# Callisto_Teknic_MSO_LED_out.net
KiCad netlist of a schematic drawn in EAGLE
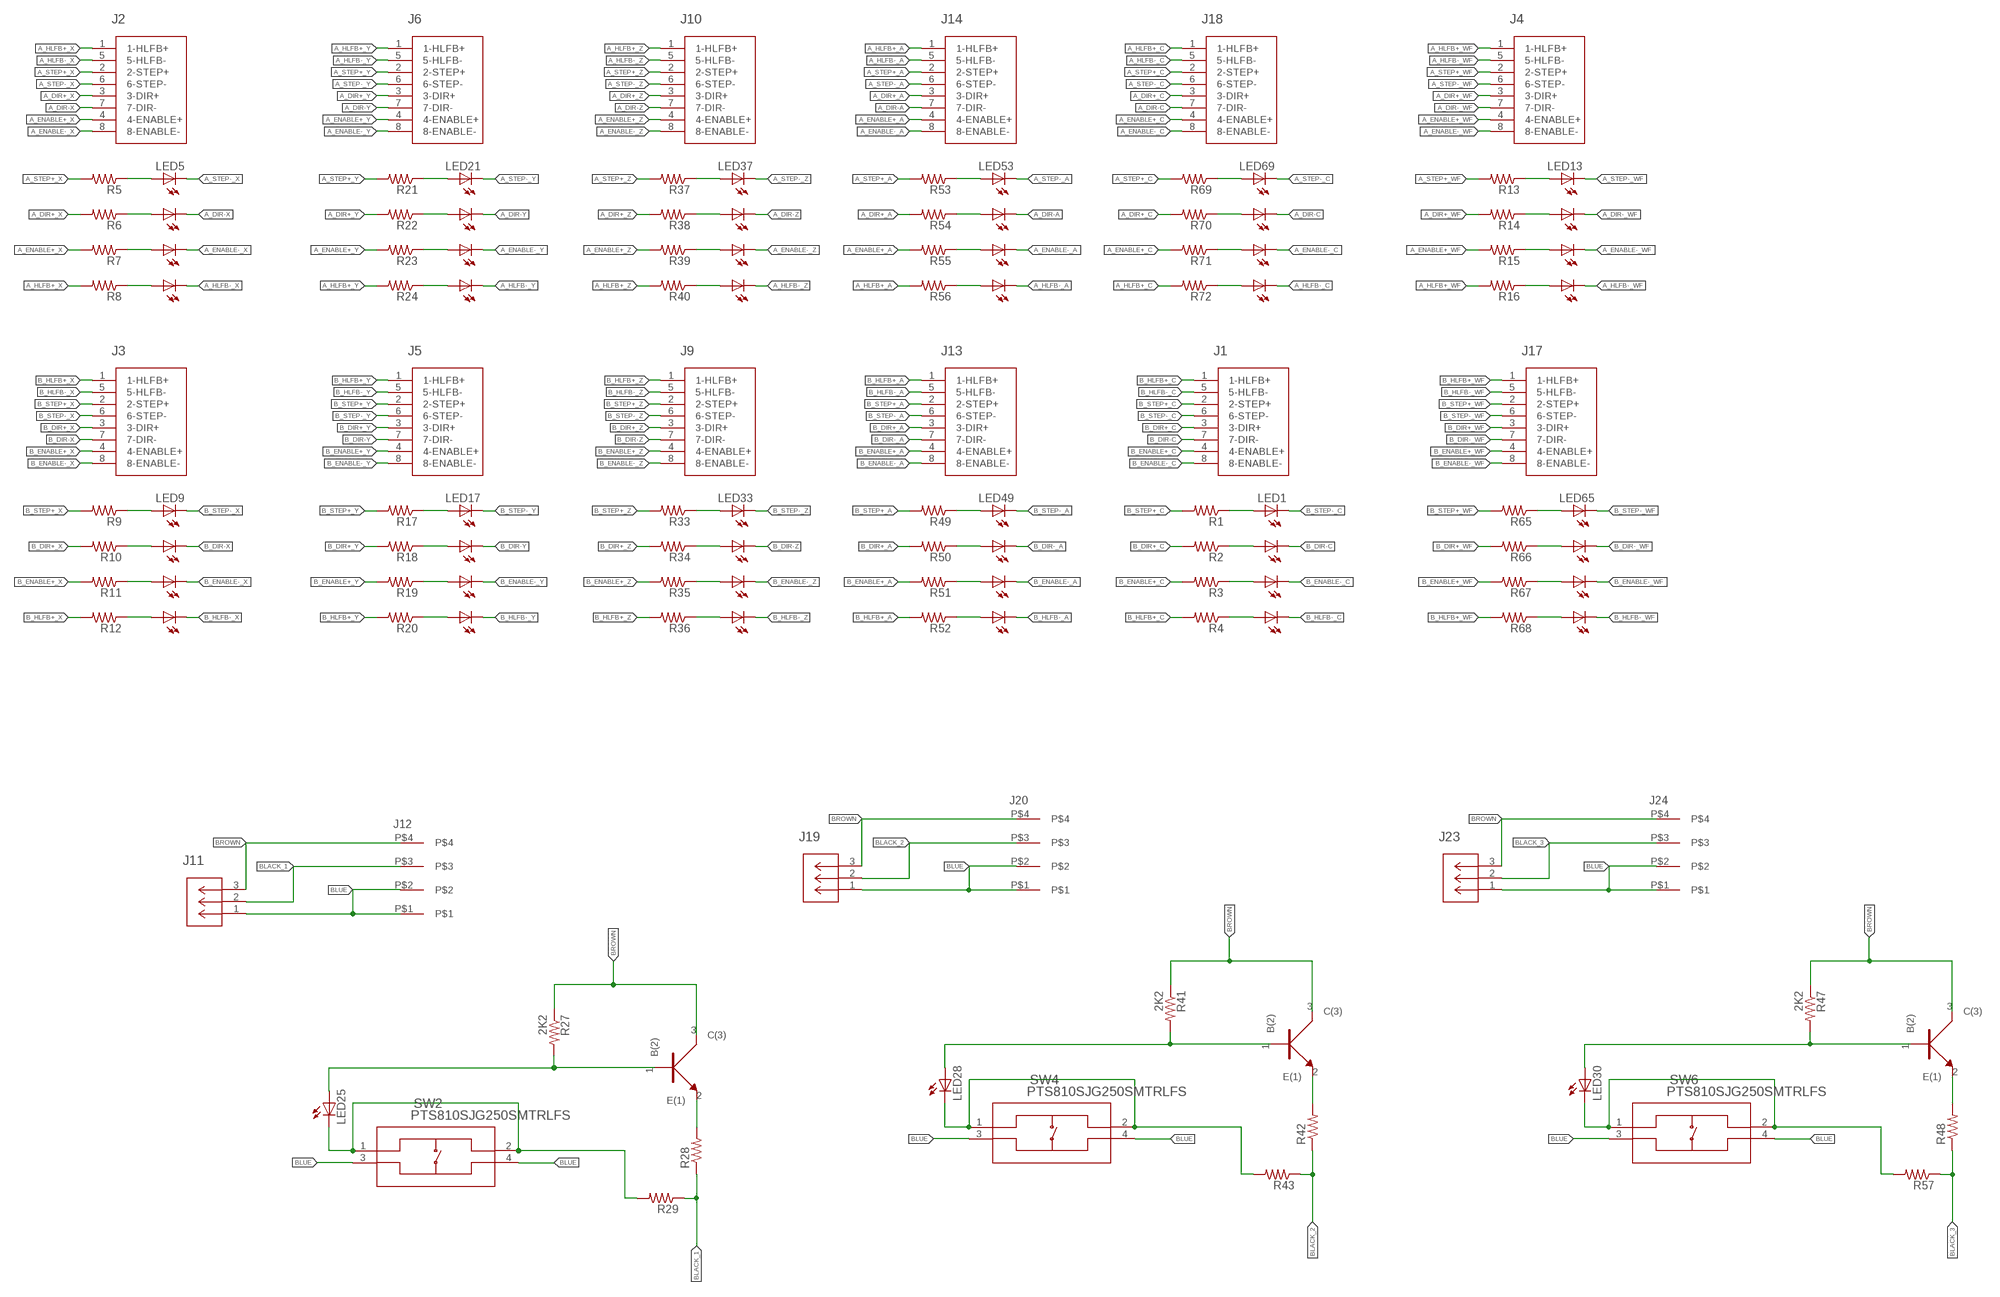
[diagram p0: schematic, sheet 1, part 1 of 2]
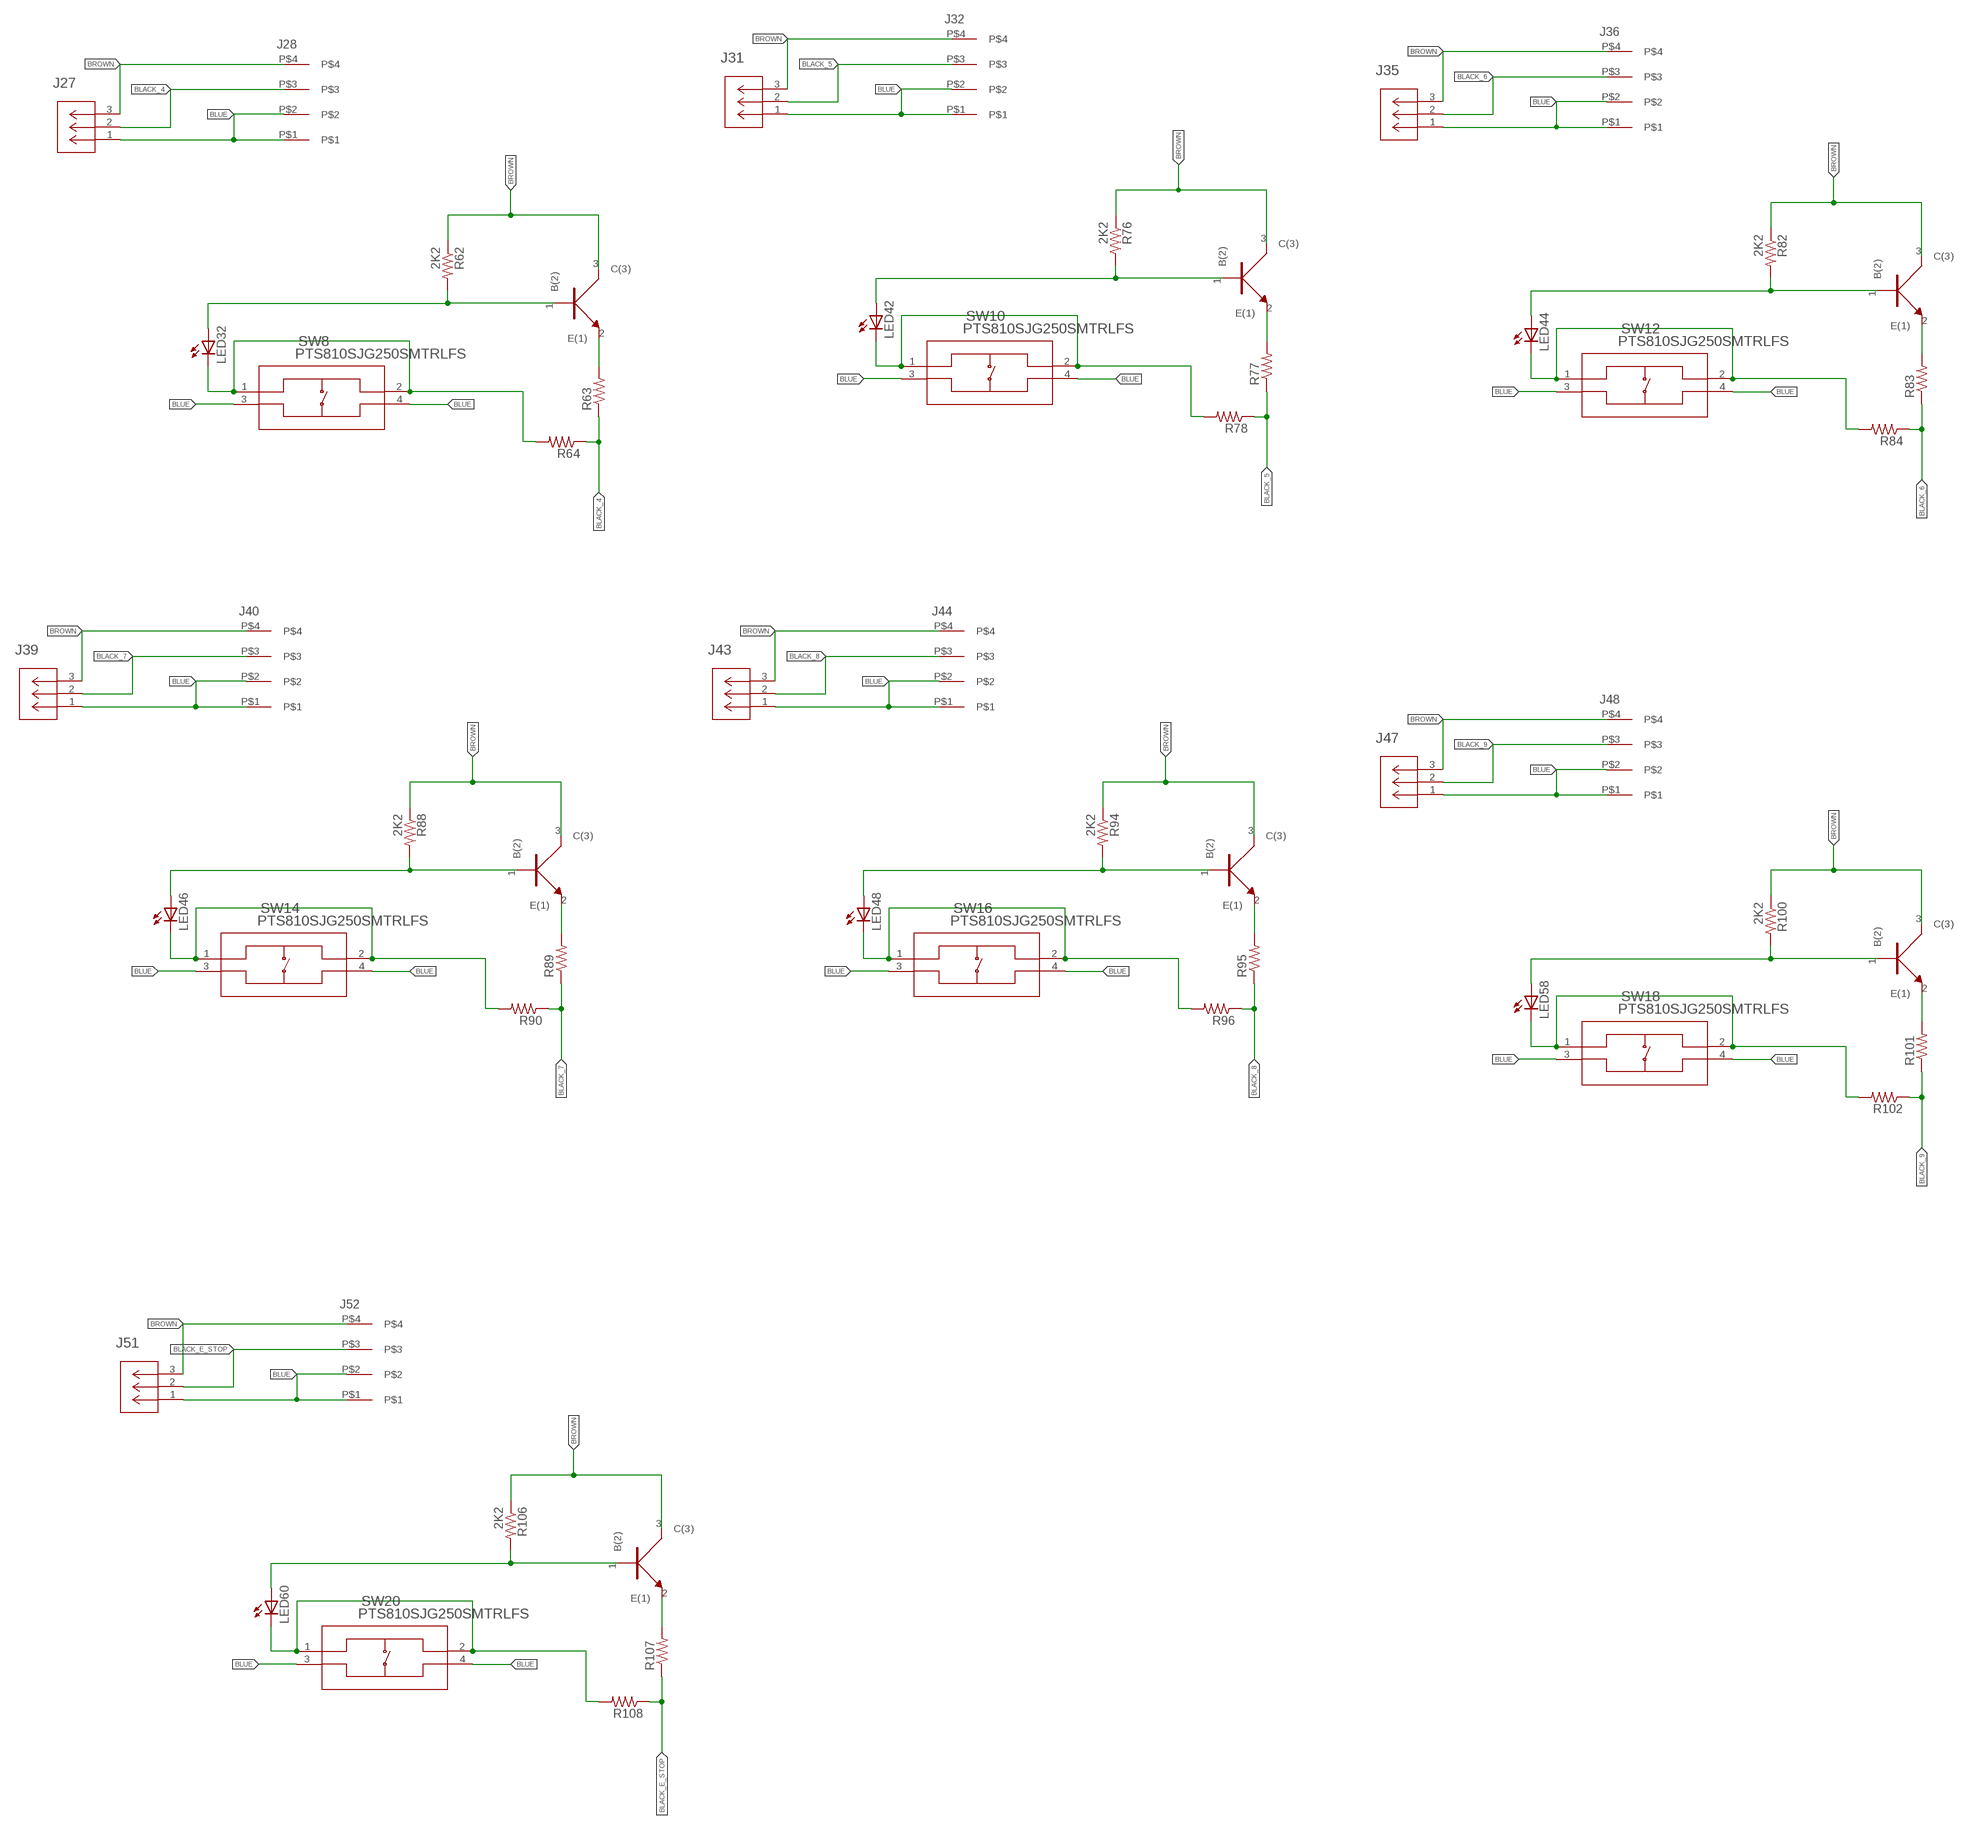
[diagram p1: schematic, sheet 1, part 2 of 2]

(export (version "E")
  (design (tool "Eeschema 10.0.6"))
  (components
    (comp (ref "J1")
      (value "TEKNIC_MOTOR_SD_8PIN")
      (footprint "eagle-import:CON_39281083")
      (fields
        (field (name "MANUFACTURER_PART_NUMBER") "39281083")
        (field (name "COPYRIGHT") "Copyright (C) 2022 Ultra Librarian. All rights reserved.")
      )
      (libsource (lib "eagle-import") (part "TEKNIC_MOTOR_SD_8PIN"))
    )
    (comp (ref "J2")
      (value "TEKNIC_MOTOR_SD_8PIN")
      (footprint "eagle-import:CON_39281083")
      (fields
        (field (name "MANUFACTURER_PART_NUMBER") "39281083")
        (field (name "COPYRIGHT") "Copyright (C) 2022 Ultra Librarian. All rights reserved.")
      )
      (libsource (lib "eagle-import") (part "TEKNIC_MOTOR_SD_8PIN"))
    )
    (comp (ref "J3")
      (value "TEKNIC_MOTOR_SD_8PIN")
      (footprint "eagle-import:CON_39281083")
      (fields
        (field (name "MANUFACTURER_PART_NUMBER") "39281083")
        (field (name "COPYRIGHT") "Copyright (C) 2022 Ultra Librarian. All rights reserved.")
      )
      (libsource (lib "eagle-import") (part "TEKNIC_MOTOR_SD_8PIN"))
    )
    (comp (ref "J4")
      (value "TEKNIC_MOTOR_SD_8PIN")
      (footprint "eagle-import:CON_39281083")
      (fields
        (field (name "MANUFACTURER_PART_NUMBER") "39281083")
        (field (name "COPYRIGHT") "Copyright (C) 2022 Ultra Librarian. All rights reserved.")
      )
      (libsource (lib "eagle-import") (part "TEKNIC_MOTOR_SD_8PIN"))
    )
    (comp (ref "J5")
      (value "TEKNIC_MOTOR_SD_8PIN")
      (footprint "eagle-import:CON_39281083")
      (fields
        (field (name "MANUFACTURER_PART_NUMBER") "39281083")
        (field (name "COPYRIGHT") "Copyright (C) 2022 Ultra Librarian. All rights reserved.")
      )
      (libsource (lib "eagle-import") (part "TEKNIC_MOTOR_SD_8PIN"))
    )
    (comp (ref "J6")
      (value "TEKNIC_MOTOR_SD_8PIN")
      (footprint "eagle-import:CON_39281083")
      (fields
        (field (name "MANUFACTURER_PART_NUMBER") "39281083")
        (field (name "COPYRIGHT") "Copyright (C) 2022 Ultra Librarian. All rights reserved.")
      )
      (libsource (lib "eagle-import") (part "TEKNIC_MOTOR_SD_8PIN"))
    )
    (comp (ref "J9")
      (value "TEKNIC_MOTOR_SD_8PIN")
      (footprint "eagle-import:CON_39281083")
      (fields
        (field (name "MANUFACTURER_PART_NUMBER") "39281083")
        (field (name "COPYRIGHT") "Copyright (C) 2022 Ultra Librarian. All rights reserved.")
      )
      (libsource (lib "eagle-import") (part "TEKNIC_MOTOR_SD_8PIN"))
    )
    (comp (ref "J10")
      (value "TEKNIC_MOTOR_SD_8PIN")
      (footprint "eagle-import:CON_39281083")
      (fields
        (field (name "MANUFACTURER_PART_NUMBER") "39281083")
        (field (name "COPYRIGHT") "Copyright (C) 2022 Ultra Librarian. All rights reserved.")
      )
      (libsource (lib "eagle-import") (part "TEKNIC_MOTOR_SD_8PIN"))
    )
    (comp (ref "J11")
      (value "CONN_530470310_PICOBLADE_X_3")
      (footprint "eagle-import:CON_530470310_MOL")
      (fields
        (field (name "MANUFACTURER_PART_NUMBER") "530470310")
        (field (name "COPYRIGHT") "Copyright (C) 2022 Ultra Librarian. All rights reserved.")
      )
      (libsource (lib "eagle-import") (part "CONN_530470310_PICOBLADE_X_3"))
    )
    (comp (ref "J12")
      (value "4-pos")
      (footprint "eagle-import:1X4_3.81MM_PITCH")
      (fields (field (name "PARTNO") "691322310004"))
      (libsource (lib "eagle-import") (part "3.81MM_1_X_4_RT_ANGLE_PLUG_HEADER"))
    )
    (comp (ref "J13")
      (value "TEKNIC_MOTOR_SD_8PIN")
      (footprint "eagle-import:CON_39281083")
      (fields
        (field (name "MANUFACTURER_PART_NUMBER") "39281083")
        (field (name "COPYRIGHT") "Copyright (C) 2022 Ultra Librarian. All rights reserved.")
      )
      (libsource (lib "eagle-import") (part "TEKNIC_MOTOR_SD_8PIN"))
    )
    (comp (ref "J14")
      (value "TEKNIC_MOTOR_SD_8PIN")
      (footprint "eagle-import:CON_39281083")
      (fields
        (field (name "MANUFACTURER_PART_NUMBER") "39281083")
        (field (name "COPYRIGHT") "Copyright (C) 2022 Ultra Librarian. All rights reserved.")
      )
      (libsource (lib "eagle-import") (part "TEKNIC_MOTOR_SD_8PIN"))
    )
    (comp (ref "J17")
      (value "TEKNIC_MOTOR_SD_8PIN")
      (footprint "eagle-import:CON_39281083")
      (fields
        (field (name "MANUFACTURER_PART_NUMBER") "39281083")
        (field (name "COPYRIGHT") "Copyright (C) 2022 Ultra Librarian. All rights reserved.")
      )
      (libsource (lib "eagle-import") (part "TEKNIC_MOTOR_SD_8PIN"))
    )
    (comp (ref "J18")
      (value "TEKNIC_MOTOR_SD_8PIN")
      (footprint "eagle-import:CON_39281083")
      (fields
        (field (name "MANUFACTURER_PART_NUMBER") "39281083")
        (field (name "COPYRIGHT") "Copyright (C) 2022 Ultra Librarian. All rights reserved.")
      )
      (libsource (lib "eagle-import") (part "TEKNIC_MOTOR_SD_8PIN"))
    )
    (comp (ref "J19")
      (value "CONN_530470310_PICOBLADE_X_3")
      (footprint "eagle-import:CON_530470310_MOL")
      (fields
        (field (name "MANUFACTURER_PART_NUMBER") "530470310")
        (field (name "COPYRIGHT") "Copyright (C) 2022 Ultra Librarian. All rights reserved.")
      )
      (libsource (lib "eagle-import") (part "CONN_530470310_PICOBLADE_X_3"))
    )
    (comp (ref "J20")
      (value "4-pos")
      (footprint "eagle-import:1X4_3.81MM_PITCH")
      (fields (field (name "PARTNO") "691322310004"))
      (libsource (lib "eagle-import") (part "3.81MM_1_X_4_RT_ANGLE_PLUG_HEADER"))
    )
    (comp (ref "J23")
      (value "CONN_530470310_PICOBLADE_X_3")
      (footprint "eagle-import:CON_530470310_MOL")
      (fields
        (field (name "MANUFACTURER_PART_NUMBER") "530470310")
        (field (name "COPYRIGHT") "Copyright (C) 2022 Ultra Librarian. All rights reserved.")
      )
      (libsource (lib "eagle-import") (part "CONN_530470310_PICOBLADE_X_3"))
    )
    (comp (ref "J24")
      (value "4-pos")
      (footprint "eagle-import:1X4_3.81MM_PITCH")
      (fields (field (name "PARTNO") "691322310004"))
      (libsource (lib "eagle-import") (part "3.81MM_1_X_4_RT_ANGLE_PLUG_HEADER"))
    )
    (comp (ref "J27")
      (value "CONN_530470310_PICOBLADE_X_3")
      (footprint "eagle-import:CON_530470310_MOL")
      (fields
        (field (name "MANUFACTURER_PART_NUMBER") "530470310")
        (field (name "COPYRIGHT") "Copyright (C) 2022 Ultra Librarian. All rights reserved.")
      )
      (libsource (lib "eagle-import") (part "CONN_530470310_PICOBLADE_X_3"))
    )
    (comp (ref "J28")
      (value "4-pos")
      (footprint "eagle-import:1X4_3.81MM_PITCH")
      (fields (field (name "PARTNO") "691322310004"))
      (libsource (lib "eagle-import") (part "3.81MM_1_X_4_RT_ANGLE_PLUG_HEADER"))
    )
    (comp (ref "J31")
      (value "CONN_530470310_PICOBLADE_X_3")
      (footprint "eagle-import:CON_530470310_MOL")
      (fields
        (field (name "MANUFACTURER_PART_NUMBER") "530470310")
        (field (name "COPYRIGHT") "Copyright (C) 2022 Ultra Librarian. All rights reserved.")
      )
      (libsource (lib "eagle-import") (part "CONN_530470310_PICOBLADE_X_3"))
    )
    (comp (ref "J32")
      (value "4-pos")
      (footprint "eagle-import:1X4_3.81MM_PITCH")
      (fields (field (name "PARTNO") "691322310004"))
      (libsource (lib "eagle-import") (part "3.81MM_1_X_4_RT_ANGLE_PLUG_HEADER"))
    )
    (comp (ref "J35")
      (value "CONN_530470310_PICOBLADE_X_3")
      (footprint "eagle-import:CON_530470310_MOL")
      (fields
        (field (name "MANUFACTURER_PART_NUMBER") "530470310")
        (field (name "COPYRIGHT") "Copyright (C) 2022 Ultra Librarian. All rights reserved.")
      )
      (libsource (lib "eagle-import") (part "CONN_530470310_PICOBLADE_X_3"))
    )
    (comp (ref "J36")
      (value "4-pos")
      (footprint "eagle-import:1X4_3.81MM_PITCH")
      (fields (field (name "PARTNO") "691322310004"))
      (libsource (lib "eagle-import") (part "3.81MM_1_X_4_RT_ANGLE_PLUG_HEADER"))
    )
    (comp (ref "J39")
      (value "CONN_530470310_PICOBLADE_X_3")
      (footprint "eagle-import:CON_530470310_MOL")
      (fields
        (field (name "MANUFACTURER_PART_NUMBER") "530470310")
        (field (name "COPYRIGHT") "Copyright (C) 2022 Ultra Librarian. All rights reserved.")
      )
      (libsource (lib "eagle-import") (part "CONN_530470310_PICOBLADE_X_3"))
    )
    (comp (ref "J40")
      (value "4-pos")
      (footprint "eagle-import:1X4_3.81MM_PITCH")
      (fields (field (name "PARTNO") "691322310004"))
      (libsource (lib "eagle-import") (part "3.81MM_1_X_4_RT_ANGLE_PLUG_HEADER"))
    )
    (comp (ref "J43")
      (value "CONN_530470310_PICOBLADE_X_3")
      (footprint "eagle-import:CON_530470310_MOL")
      (fields
        (field (name "MANUFACTURER_PART_NUMBER") "530470310")
        (field (name "COPYRIGHT") "Copyright (C) 2022 Ultra Librarian. All rights reserved.")
      )
      (libsource (lib "eagle-import") (part "CONN_530470310_PICOBLADE_X_3"))
    )
    (comp (ref "J44")
      (value "4-pos")
      (footprint "eagle-import:1X4_3.81MM_PITCH")
      (fields (field (name "PARTNO") "691322310004"))
      (libsource (lib "eagle-import") (part "3.81MM_1_X_4_RT_ANGLE_PLUG_HEADER"))
    )
    (comp (ref "J47")
      (value "CONN_530470310_PICOBLADE_X_3")
      (footprint "eagle-import:CON_530470310_MOL")
      (fields
        (field (name "MANUFACTURER_PART_NUMBER") "530470310")
        (field (name "COPYRIGHT") "Copyright (C) 2022 Ultra Librarian. All rights reserved.")
      )
      (libsource (lib "eagle-import") (part "CONN_530470310_PICOBLADE_X_3"))
    )
    (comp (ref "J48")
      (value "4-pos")
      (footprint "eagle-import:1X4_3.81MM_PITCH")
      (fields (field (name "PARTNO") "691322310004"))
      (libsource (lib "eagle-import") (part "3.81MM_1_X_4_RT_ANGLE_PLUG_HEADER"))
    )
    (comp (ref "J51")
      (value "CONN_530470310_PICOBLADE_X_3")
      (footprint "eagle-import:CON_530470310_MOL")
      (fields
        (field (name "MANUFACTURER_PART_NUMBER") "530470310")
        (field (name "COPYRIGHT") "Copyright (C) 2022 Ultra Librarian. All rights reserved.")
      )
      (libsource (lib "eagle-import") (part "CONN_530470310_PICOBLADE_X_3"))
    )
    (comp (ref "J52")
      (value "4-pos")
      (footprint "eagle-import:1X4_3.81MM_PITCH")
      (fields (field (name "PARTNO") "691322310004"))
      (libsource (lib "eagle-import") (part "3.81MM_1_X_4_RT_ANGLE_PLUG_HEADER"))
    )
    (comp (ref "LED1")
      (value "Green")
      (footprint "eagle-import:0805")
      (fields (field (name "PARTNO") "LG R971-KN-1"))
      (libsource (lib "eagle-import") (part "LED_0805_GREEN"))
    )
    (comp (ref "LED2")
      (value "Green")
      (footprint "eagle-import:0805")
      (fields (field (name "PARTNO") "LG R971-KN-1"))
      (libsource (lib "eagle-import") (part "LED_0805_GREEN"))
    )
    (comp (ref "LED3")
      (value "Green")
      (footprint "eagle-import:0805")
      (fields (field (name "PARTNO") "LG R971-KN-1"))
      (libsource (lib "eagle-import") (part "LED_0805_GREEN"))
    )
    (comp (ref "LED4")
      (value "Green")
      (footprint "eagle-import:0805")
      (fields (field (name "PARTNO") "LG R971-KN-1"))
      (libsource (lib "eagle-import") (part "LED_0805_GREEN"))
    )
    (comp (ref "LED5")
      (value "Green")
      (footprint "eagle-import:0805")
      (fields (field (name "PARTNO") "LG R971-KN-1"))
      (libsource (lib "eagle-import") (part "LED_0805_GREEN"))
    )
    (comp (ref "LED6")
      (value "Green")
      (footprint "eagle-import:0805")
      (fields (field (name "PARTNO") "LG R971-KN-1"))
      (libsource (lib "eagle-import") (part "LED_0805_GREEN"))
    )
    (comp (ref "LED7")
      (value "Green")
      (footprint "eagle-import:0805")
      (fields (field (name "PARTNO") "LG R971-KN-1"))
      (libsource (lib "eagle-import") (part "LED_0805_GREEN"))
    )
    (comp (ref "LED8")
      (value "Green")
      (footprint "eagle-import:0805")
      (fields (field (name "PARTNO") "LG R971-KN-1"))
      (libsource (lib "eagle-import") (part "LED_0805_GREEN"))
    )
    (comp (ref "LED9")
      (value "Green")
      (footprint "eagle-import:0805")
      (fields (field (name "PARTNO") "LG R971-KN-1"))
      (libsource (lib "eagle-import") (part "LED_0805_GREEN"))
    )
    (comp (ref "LED10")
      (value "Green")
      (footprint "eagle-import:0805")
      (fields (field (name "PARTNO") "LG R971-KN-1"))
      (libsource (lib "eagle-import") (part "LED_0805_GREEN"))
    )
    (comp (ref "LED11")
      (value "Green")
      (footprint "eagle-import:0805")
      (fields (field (name "PARTNO") "LG R971-KN-1"))
      (libsource (lib "eagle-import") (part "LED_0805_GREEN"))
    )
    (comp (ref "LED12")
      (value "Green")
      (footprint "eagle-import:0805")
      (fields (field (name "PARTNO") "LG R971-KN-1"))
      (libsource (lib "eagle-import") (part "LED_0805_GREEN"))
    )
    (comp (ref "LED13")
      (value "Green")
      (footprint "eagle-import:0805")
      (fields (field (name "PARTNO") "LG R971-KN-1"))
      (libsource (lib "eagle-import") (part "LED_0805_GREEN"))
    )
    (comp (ref "LED14")
      (value "Green")
      (footprint "eagle-import:0805")
      (fields (field (name "PARTNO") "LG R971-KN-1"))
      (libsource (lib "eagle-import") (part "LED_0805_GREEN"))
    )
    (comp (ref "LED15")
      (value "Green")
      (footprint "eagle-import:0805")
      (fields (field (name "PARTNO") "LG R971-KN-1"))
      (libsource (lib "eagle-import") (part "LED_0805_GREEN"))
    )
    (comp (ref "LED16")
      (value "Green")
      (footprint "eagle-import:0805")
      (fields (field (name "PARTNO") "LG R971-KN-1"))
      (libsource (lib "eagle-import") (part "LED_0805_GREEN"))
    )
    (comp (ref "LED17")
      (value "Green")
      (footprint "eagle-import:0805")
      (fields (field (name "PARTNO") "LG R971-KN-1"))
      (libsource (lib "eagle-import") (part "LED_0805_GREEN"))
    )
    (comp (ref "LED18")
      (value "Green")
      (footprint "eagle-import:0805")
      (fields (field (name "PARTNO") "LG R971-KN-1"))
      (libsource (lib "eagle-import") (part "LED_0805_GREEN"))
    )
    (comp (ref "LED19")
      (value "Green")
      (footprint "eagle-import:0805")
      (fields (field (name "PARTNO") "LG R971-KN-1"))
      (libsource (lib "eagle-import") (part "LED_0805_GREEN"))
    )
    (comp (ref "LED20")
      (value "Green")
      (footprint "eagle-import:0805")
      (fields (field (name "PARTNO") "LG R971-KN-1"))
      (libsource (lib "eagle-import") (part "LED_0805_GREEN"))
    )
    (comp (ref "LED21")
      (value "Green")
      (footprint "eagle-import:0805")
      (fields (field (name "PARTNO") "LG R971-KN-1"))
      (libsource (lib "eagle-import") (part "LED_0805_GREEN"))
    )
    (comp (ref "LED22")
      (value "Green")
      (footprint "eagle-import:0805")
      (fields (field (name "PARTNO") "LG R971-KN-1"))
      (libsource (lib "eagle-import") (part "LED_0805_GREEN"))
    )
    (comp (ref "LED23")
      (value "Green")
      (footprint "eagle-import:0805")
      (fields (field (name "PARTNO") "LG R971-KN-1"))
      (libsource (lib "eagle-import") (part "LED_0805_GREEN"))
    )
    (comp (ref "LED24")
      (value "Green")
      (footprint "eagle-import:0805")
      (fields (field (name "PARTNO") "LG R971-KN-1"))
      (libsource (lib "eagle-import") (part "LED_0805_GREEN"))
    )
    (comp (ref "LED25")
      (value "Green")
      (footprint "eagle-import:0805")
      (fields (field (name "PARTNO") "LG R971-KN-1"))
      (libsource (lib "eagle-import") (part "LED_0805_GREEN"))
    )
    (comp (ref "LED28")
      (value "Green")
      (footprint "eagle-import:0805")
      (fields (field (name "PARTNO") "LG R971-KN-1"))
      (libsource (lib "eagle-import") (part "LED_0805_GREEN"))
    )
    (comp (ref "LED30")
      (value "Green")
      (footprint "eagle-import:0805")
      (fields (field (name "PARTNO") "LG R971-KN-1"))
      (libsource (lib "eagle-import") (part "LED_0805_GREEN"))
    )
    (comp (ref "LED32")
      (value "Green")
      (footprint "eagle-import:0805")
      (fields (field (name "PARTNO") "LG R971-KN-1"))
      (libsource (lib "eagle-import") (part "LED_0805_GREEN"))
    )
    (comp (ref "LED33")
      (value "Green")
      (footprint "eagle-import:0805")
      (fields (field (name "PARTNO") "LG R971-KN-1"))
      (libsource (lib "eagle-import") (part "LED_0805_GREEN"))
    )
    (comp (ref "LED34")
      (value "Green")
      (footprint "eagle-import:0805")
      (fields (field (name "PARTNO") "LG R971-KN-1"))
      (libsource (lib "eagle-import") (part "LED_0805_GREEN"))
    )
    (comp (ref "LED35")
      (value "Green")
      (footprint "eagle-import:0805")
      (fields (field (name "PARTNO") "LG R971-KN-1"))
      (libsource (lib "eagle-import") (part "LED_0805_GREEN"))
    )
    (comp (ref "LED36")
      (value "Green")
      (footprint "eagle-import:0805")
      (fields (field (name "PARTNO") "LG R971-KN-1"))
      (libsource (lib "eagle-import") (part "LED_0805_GREEN"))
    )
    (comp (ref "LED37")
      (value "Green")
      (footprint "eagle-import:0805")
      (fields (field (name "PARTNO") "LG R971-KN-1"))
      (libsource (lib "eagle-import") (part "LED_0805_GREEN"))
    )
    (comp (ref "LED38")
      (value "Green")
      (footprint "eagle-import:0805")
      (fields (field (name "PARTNO") "LG R971-KN-1"))
      (libsource (lib "eagle-import") (part "LED_0805_GREEN"))
    )
    (comp (ref "LED39")
      (value "Green")
      (footprint "eagle-import:0805")
      (fields (field (name "PARTNO") "LG R971-KN-1"))
      (libsource (lib "eagle-import") (part "LED_0805_GREEN"))
    )
    (comp (ref "LED40")
      (value "Green")
      (footprint "eagle-import:0805")
      (fields (field (name "PARTNO") "LG R971-KN-1"))
      (libsource (lib "eagle-import") (part "LED_0805_GREEN"))
    )
    (comp (ref "LED42")
      (value "Green")
      (footprint "eagle-import:0805")
      (fields (field (name "PARTNO") "LG R971-KN-1"))
      (libsource (lib "eagle-import") (part "LED_0805_GREEN"))
    )
    (comp (ref "LED44")
      (value "Green")
      (footprint "eagle-import:0805")
      (fields (field (name "PARTNO") "LG R971-KN-1"))
      (libsource (lib "eagle-import") (part "LED_0805_GREEN"))
    )
    (comp (ref "LED46")
      (value "Green")
      (footprint "eagle-import:0805")
      (fields (field (name "PARTNO") "LG R971-KN-1"))
      (libsource (lib "eagle-import") (part "LED_0805_GREEN"))
    )
    (comp (ref "LED48")
      (value "Green")
      (footprint "eagle-import:0805")
      (fields (field (name "PARTNO") "LG R971-KN-1"))
      (libsource (lib "eagle-import") (part "LED_0805_GREEN"))
    )
    (comp (ref "LED49")
      (value "Green")
      (footprint "eagle-import:0805")
      (fields (field (name "PARTNO") "LG R971-KN-1"))
      (libsource (lib "eagle-import") (part "LED_0805_GREEN"))
    )
    (comp (ref "LED50")
      (value "Green")
      (footprint "eagle-import:0805")
      (fields (field (name "PARTNO") "LG R971-KN-1"))
      (libsource (lib "eagle-import") (part "LED_0805_GREEN"))
    )
    (comp (ref "LED51")
      (value "Green")
      (footprint "eagle-import:0805")
      (fields (field (name "PARTNO") "LG R971-KN-1"))
      (libsource (lib "eagle-import") (part "LED_0805_GREEN"))
    )
    (comp (ref "LED52")
      (value "Green")
      (footprint "eagle-import:0805")
      (fields (field (name "PARTNO") "LG R971-KN-1"))
      (libsource (lib "eagle-import") (part "LED_0805_GREEN"))
    )
    (comp (ref "LED53")
      (value "Green")
      (footprint "eagle-import:0805")
      (fields (field (name "PARTNO") "LG R971-KN-1"))
      (libsource (lib "eagle-import") (part "LED_0805_GREEN"))
    )
    (comp (ref "LED54")
      (value "Green")
      (footprint "eagle-import:0805")
      (fields (field (name "PARTNO") "LG R971-KN-1"))
      (libsource (lib "eagle-import") (part "LED_0805_GREEN"))
    )
    (comp (ref "LED55")
      (value "Green")
      (footprint "eagle-import:0805")
      (fields (field (name "PARTNO") "LG R971-KN-1"))
      (libsource (lib "eagle-import") (part "LED_0805_GREEN"))
    )
    (comp (ref "LED56")
      (value "Green")
      (footprint "eagle-import:0805")
      (fields (field (name "PARTNO") "LG R971-KN-1"))
      (libsource (lib "eagle-import") (part "LED_0805_GREEN"))
    )
    (comp (ref "LED58")
      (value "Green")
      (footprint "eagle-import:0805")
      (fields (field (name "PARTNO") "LG R971-KN-1"))
      (libsource (lib "eagle-import") (part "LED_0805_GREEN"))
    )
    (comp (ref "LED60")
      (value "Green")
      (footprint "eagle-import:0805")
      (fields (field (name "PARTNO") "LG R971-KN-1"))
      (libsource (lib "eagle-import") (part "LED_0805_GREEN"))
    )
    (comp (ref "LED65")
      (value "Green")
      (footprint "eagle-import:0805")
      (fields (field (name "PARTNO") "LG R971-KN-1"))
      (libsource (lib "eagle-import") (part "LED_0805_GREEN"))
    )
    (comp (ref "LED66")
      (value "Green")
      (footprint "eagle-import:0805")
      (fields (field (name "PARTNO") "LG R971-KN-1"))
      (libsource (lib "eagle-import") (part "LED_0805_GREEN"))
    )
    (comp (ref "LED67")
      (value "Green")
      (footprint "eagle-import:0805")
      (fields (field (name "PARTNO") "LG R971-KN-1"))
      (libsource (lib "eagle-import") (part "LED_0805_GREEN"))
    )
    (comp (ref "LED68")
      (value "Green")
      (footprint "eagle-import:0805")
      (fields (field (name "PARTNO") "LG R971-KN-1"))
      (libsource (lib "eagle-import") (part "LED_0805_GREEN"))
    )
    (comp (ref "LED69")
      (value "Green")
      (footprint "eagle-import:0805")
      (fields (field (name "PARTNO") "LG R971-KN-1"))
      (libsource (lib "eagle-import") (part "LED_0805_GREEN"))
    )
    (comp (ref "LED70")
      (value "Green")
      (footprint "eagle-import:0805")
      (fields (field (name "PARTNO") "LG R971-KN-1"))
      (libsource (lib "eagle-import") (part "LED_0805_GREEN"))
    )
    (comp (ref "LED71")
      (value "Green")
      (footprint "eagle-import:0805")
      (fields (field (name "PARTNO") "LG R971-KN-1"))
      (libsource (lib "eagle-import") (part "LED_0805_GREEN"))
    )
    (comp (ref "LED72")
      (value "Green")
      (footprint "eagle-import:0805")
      (fields (field (name "PARTNO") "LG R971-KN-1"))
      (libsource (lib "eagle-import") (part "LED_0805_GREEN"))
    )
    (comp (ref "R1")
      (value "R_0805")
      (footprint "eagle-import:0805")
      (libsource (lib "eagle-import") (part "R_0805"))
    )
    (comp (ref "R2")
      (value "R_0805")
      (footprint "eagle-import:0805")
      (libsource (lib "eagle-import") (part "R_0805"))
    )
    (comp (ref "R3")
      (value "R_0805")
      (footprint "eagle-import:0805")
      (libsource (lib "eagle-import") (part "R_0805"))
    )
    (comp (ref "R4")
      (value "R_0805")
      (footprint "eagle-import:0805")
      (libsource (lib "eagle-import") (part "R_0805"))
    )
    (comp (ref "R5")
      (value "R_0805")
      (footprint "eagle-import:0805")
      (libsource (lib "eagle-import") (part "R_0805"))
    )
    (comp (ref "R6")
      (value "R_0805")
      (footprint "eagle-import:0805")
      (libsource (lib "eagle-import") (part "R_0805"))
    )
    (comp (ref "R7")
      (value "R_0805")
      (footprint "eagle-import:0805")
      (libsource (lib "eagle-import") (part "R_0805"))
    )
    (comp (ref "R8")
      (value "R_0805")
      (footprint "eagle-import:0805")
      (libsource (lib "eagle-import") (part "R_0805"))
    )
    (comp (ref "R9")
      (value "R_0805")
      (footprint "eagle-import:0805")
      (libsource (lib "eagle-import") (part "R_0805"))
    )
    (comp (ref "R10")
      (value "R_0805")
      (footprint "eagle-import:0805")
      (libsource (lib "eagle-import") (part "R_0805"))
    )
    (comp (ref "R11")
      (value "R_0805")
      (footprint "eagle-import:0805")
      (libsource (lib "eagle-import") (part "R_0805"))
    )
    (comp (ref "R12")
      (value "R_0805")
      (footprint "eagle-import:0805")
      (libsource (lib "eagle-import") (part "R_0805"))
    )
    (comp (ref "R13")
      (value "R_0805")
      (footprint "eagle-import:0805")
      (libsource (lib "eagle-import") (part "R_0805"))
    )
    (comp (ref "R14")
      (value "R_0805")
      (footprint "eagle-import:0805")
      (libsource (lib "eagle-import") (part "R_0805"))
    )
    (comp (ref "R15")
      (value "R_0805")
      (footprint "eagle-import:0805")
      (libsource (lib "eagle-import") (part "R_0805"))
    )
    (comp (ref "R16")
      (value "R_0805")
      (footprint "eagle-import:0805")
      (libsource (lib "eagle-import") (part "R_0805"))
    )
    (comp (ref "R17")
      (value "R_0805")
      (footprint "eagle-import:0805")
      (libsource (lib "eagle-import") (part "R_0805"))
    )
    (comp (ref "R18")
      (value "R_0805")
      (footprint "eagle-import:0805")
      (libsource (lib "eagle-import") (part "R_0805"))
    )
    (comp (ref "R19")
      (value "R_0805")
      (footprint "eagle-import:0805")
      (libsource (lib "eagle-import") (part "R_0805"))
    )
    (comp (ref "R20")
      (value "R_0805")
      (footprint "eagle-import:0805")
      (libsource (lib "eagle-import") (part "R_0805"))
    )
    (comp (ref "R21")
      (value "R_0805")
      (footprint "eagle-import:0805")
      (libsource (lib "eagle-import") (part "R_0805"))
    )
    (comp (ref "R22")
      (value "R_0805")
      (footprint "eagle-import:0805")
      (libsource (lib "eagle-import") (part "R_0805"))
    )
    (comp (ref "R23")
      (value "R_0805")
      (footprint "eagle-import:0805")
      (libsource (lib "eagle-import") (part "R_0805"))
    )
    (comp (ref "R24")
      (value "R_0805")
      (footprint "eagle-import:0805")
      (libsource (lib "eagle-import") (part "R_0805"))
    )
    (comp (ref "R27")
      (value "2K2")
      (footprint "eagle-import:0402")
      (libsource (lib "eagle-import") (part "R_0402"))
    )
    (comp (ref "R28")
      (value "R_0402")
      (footprint "eagle-import:0402")
      (libsource (lib "eagle-import") (part "R_0402"))
    )
    (comp (ref "R29")
      (value "R_0402")
      (footprint "eagle-import:0402")
      (libsource (lib "eagle-import") (part "R_0402"))
    )
    (comp (ref "R33")
      (value "R_0805")
      (footprint "eagle-import:0805")
      (libsource (lib "eagle-import") (part "R_0805"))
    )
    (comp (ref "R34")
      (value "R_0805")
      (footprint "eagle-import:0805")
      (libsource (lib "eagle-import") (part "R_0805"))
    )
    (comp (ref "R35")
      (value "R_0805")
      (footprint "eagle-import:0805")
      (libsource (lib "eagle-import") (part "R_0805"))
    )
    (comp (ref "R36")
      (value "R_0805")
      (footprint "eagle-import:0805")
      (libsource (lib "eagle-import") (part "R_0805"))
    )
    (comp (ref "R37")
      (value "R_0805")
      (footprint "eagle-import:0805")
      (libsource (lib "eagle-import") (part "R_0805"))
    )
    (comp (ref "R38")
      (value "R_0805")
      (footprint "eagle-import:0805")
      (libsource (lib "eagle-import") (part "R_0805"))
    )
    (comp (ref "R39")
      (value "R_0805")
      (footprint "eagle-import:0805")
      (libsource (lib "eagle-import") (part "R_0805"))
    )
    (comp (ref "R40")
      (value "R_0805")
      (footprint "eagle-import:0805")
      (libsource (lib "eagle-import") (part "R_0805"))
    )
    (comp (ref "R41")
      (value "2K2")
      (footprint "eagle-import:0402")
      (libsource (lib "eagle-import") (part "R_0402"))
    )
    (comp (ref "R42")
      (value "R_0402")
      (footprint "eagle-import:0402")
      (libsource (lib "eagle-import") (part "R_0402"))
    )
    (comp (ref "R43")
      (value "R_0402")
      (footprint "eagle-import:0402")
      (libsource (lib "eagle-import") (part "R_0402"))
    )
    (comp (ref "R47")
      (value "2K2")
      (footprint "eagle-import:0402")
      (libsource (lib "eagle-import") (part "R_0402"))
    )
    (comp (ref "R48")
      (value "R_0402")
      (footprint "eagle-import:0402")
      (libsource (lib "eagle-import") (part "R_0402"))
    )
    (comp (ref "R49")
      (value "R_0805")
      (footprint "eagle-import:0805")
      (libsource (lib "eagle-import") (part "R_0805"))
    )
    (comp (ref "R50")
      (value "R_0805")
      (footprint "eagle-import:0805")
      (libsource (lib "eagle-import") (part "R_0805"))
    )
    (comp (ref "R51")
      (value "R_0805")
      (footprint "eagle-import:0805")
      (libsource (lib "eagle-import") (part "R_0805"))
    )
    (comp (ref "R52")
      (value "R_0805")
      (footprint "eagle-import:0805")
      (libsource (lib "eagle-import") (part "R_0805"))
    )
    (comp (ref "R53")
      (value "R_0805")
      (footprint "eagle-import:0805")
      (libsource (lib "eagle-import") (part "R_0805"))
    )
    (comp (ref "R54")
      (value "R_0805")
      (footprint "eagle-import:0805")
      (libsource (lib "eagle-import") (part "R_0805"))
    )
    (comp (ref "R55")
      (value "R_0805")
      (footprint "eagle-import:0805")
      (libsource (lib "eagle-import") (part "R_0805"))
    )
    (comp (ref "R56")
      (value "R_0805")
      (footprint "eagle-import:0805")
      (libsource (lib "eagle-import") (part "R_0805"))
    )
    (comp (ref "R57")
      (value "R_0402")
      (footprint "eagle-import:0402")
      (libsource (lib "eagle-import") (part "R_0402"))
    )
    (comp (ref "R62")
      (value "2K2")
      (footprint "eagle-import:0402")
      (libsource (lib "eagle-import") (part "R_0402"))
    )
    (comp (ref "R63")
      (value "R_0402")
      (footprint "eagle-import:0402")
      (libsource (lib "eagle-import") (part "R_0402"))
    )
    (comp (ref "R64")
      (value "R_0402")
      (footprint "eagle-import:0402")
      (libsource (lib "eagle-import") (part "R_0402"))
    )
    (comp (ref "R65")
      (value "R_0805")
      (footprint "eagle-import:0805")
      (libsource (lib "eagle-import") (part "R_0805"))
    )
    (comp (ref "R66")
      (value "R_0805")
      (footprint "eagle-import:0805")
      (libsource (lib "eagle-import") (part "R_0805"))
    )
    (comp (ref "R67")
      (value "R_0805")
      (footprint "eagle-import:0805")
      (libsource (lib "eagle-import") (part "R_0805"))
    )
    (comp (ref "R68")
      (value "R_0805")
      (footprint "eagle-import:0805")
      (libsource (lib "eagle-import") (part "R_0805"))
    )
    (comp (ref "R69")
      (value "R_0805")
      (footprint "eagle-import:0805")
      (libsource (lib "eagle-import") (part "R_0805"))
    )
    (comp (ref "R70")
      (value "R_0805")
      (footprint "eagle-import:0805")
      (libsource (lib "eagle-import") (part "R_0805"))
    )
    (comp (ref "R71")
      (value "R_0805")
      (footprint "eagle-import:0805")
      (libsource (lib "eagle-import") (part "R_0805"))
    )
    (comp (ref "R72")
      (value "R_0805")
      (footprint "eagle-import:0805")
      (libsource (lib "eagle-import") (part "R_0805"))
    )
    (comp (ref "R76")
      (value "2K2")
      (footprint "eagle-import:0402")
      (libsource (lib "eagle-import") (part "R_0402"))
    )
    (comp (ref "R77")
      (value "R_0402")
      (footprint "eagle-import:0402")
      (libsource (lib "eagle-import") (part "R_0402"))
    )
    (comp (ref "R78")
      (value "R_0402")
      (footprint "eagle-import:0402")
      (libsource (lib "eagle-import") (part "R_0402"))
    )
    (comp (ref "R82")
      (value "2K2")
      (footprint "eagle-import:0402")
      (libsource (lib "eagle-import") (part "R_0402"))
    )
    (comp (ref "R83")
      (value "R_0402")
      (footprint "eagle-import:0402")
      (libsource (lib "eagle-import") (part "R_0402"))
    )
    (comp (ref "R84")
      (value "R_0402")
      (footprint "eagle-import:0402")
      (libsource (lib "eagle-import") (part "R_0402"))
    )
    (comp (ref "R88")
      (value "2K2")
      (footprint "eagle-import:0402")
      (libsource (lib "eagle-import") (part "R_0402"))
    )
    (comp (ref "R89")
      (value "R_0402")
      (footprint "eagle-import:0402")
      (libsource (lib "eagle-import") (part "R_0402"))
    )
    (comp (ref "R90")
      (value "R_0402")
      (footprint "eagle-import:0402")
      (libsource (lib "eagle-import") (part "R_0402"))
    )
    (comp (ref "R94")
      (value "2K2")
      (footprint "eagle-import:0402")
      (libsource (lib "eagle-import") (part "R_0402"))
    )
    (comp (ref "R95")
      (value "R_0402")
      (footprint "eagle-import:0402")
      (libsource (lib "eagle-import") (part "R_0402"))
    )
    (comp (ref "R96")
      (value "R_0402")
      (footprint "eagle-import:0402")
      (libsource (lib "eagle-import") (part "R_0402"))
    )
    (comp (ref "R100")
      (value "2K2")
      (footprint "eagle-import:0402")
      (libsource (lib "eagle-import") (part "R_0402"))
    )
    (comp (ref "R101")
      (value "R_0402")
      (footprint "eagle-import:0402")
      (libsource (lib "eagle-import") (part "R_0402"))
    )
    (comp (ref "R102")
      (value "R_0402")
      (footprint "eagle-import:0402")
      (libsource (lib "eagle-import") (part "R_0402"))
    )
    (comp (ref "R106")
      (value "2K2")
      (footprint "eagle-import:0402")
      (libsource (lib "eagle-import") (part "R_0402"))
    )
    (comp (ref "R107")
      (value "R_0402")
      (footprint "eagle-import:0402")
      (libsource (lib "eagle-import") (part "R_0402"))
    )
    (comp (ref "R108")
      (value "R_0402")
      (footprint "eagle-import:0402")
      (libsource (lib "eagle-import") (part "R_0402"))
    )
    (comp (ref "SW2")
      (value "PTS810SJG250SMTRLFS")
      (footprint "eagle-import:PTS810")
      (fields (field (name "COPYRIGHT") "Copyright (C) 2018 Accelerated Designs. All rights reserved"))
      (libsource (lib "eagle-import") (part "PTS810SJG250SMTRLFS"))
    )
    (comp (ref "SW4")
      (value "PTS810SJG250SMTRLFS")
      (footprint "eagle-import:PTS810")
      (fields (field (name "COPYRIGHT") "Copyright (C) 2018 Accelerated Designs. All rights reserved"))
      (libsource (lib "eagle-import") (part "PTS810SJG250SMTRLFS"))
    )
    (comp (ref "SW6")
      (value "PTS810SJG250SMTRLFS")
      (footprint "eagle-import:PTS810")
      (fields (field (name "COPYRIGHT") "Copyright (C) 2018 Accelerated Designs. All rights reserved"))
      (libsource (lib "eagle-import") (part "PTS810SJG250SMTRLFS"))
    )
    (comp (ref "SW8")
      (value "PTS810SJG250SMTRLFS")
      (footprint "eagle-import:PTS810")
      (fields (field (name "COPYRIGHT") "Copyright (C) 2018 Accelerated Designs. All rights reserved"))
      (libsource (lib "eagle-import") (part "PTS810SJG250SMTRLFS"))
    )
    (comp (ref "SW10")
      (value "PTS810SJG250SMTRLFS")
      (footprint "eagle-import:PTS810")
      (fields (field (name "COPYRIGHT") "Copyright (C) 2018 Accelerated Designs. All rights reserved"))
      (libsource (lib "eagle-import") (part "PTS810SJG250SMTRLFS"))
    )
    (comp (ref "SW12")
      (value "PTS810SJG250SMTRLFS")
      (footprint "eagle-import:PTS810")
      (fields (field (name "COPYRIGHT") "Copyright (C) 2018 Accelerated Designs. All rights reserved"))
      (libsource (lib "eagle-import") (part "PTS810SJG250SMTRLFS"))
    )
    (comp (ref "SW14")
      (value "PTS810SJG250SMTRLFS")
      (footprint "eagle-import:PTS810")
      (fields (field (name "COPYRIGHT") "Copyright (C) 2018 Accelerated Designs. All rights reserved"))
      (libsource (lib "eagle-import") (part "PTS810SJG250SMTRLFS"))
    )
    (comp (ref "SW16")
      (value "PTS810SJG250SMTRLFS")
      (footprint "eagle-import:PTS810")
      (fields (field (name "COPYRIGHT") "Copyright (C) 2018 Accelerated Designs. All rights reserved"))
      (libsource (lib "eagle-import") (part "PTS810SJG250SMTRLFS"))
    )
    (comp (ref "SW18")
      (value "PTS810SJG250SMTRLFS")
      (footprint "eagle-import:PTS810")
      (fields (field (name "COPYRIGHT") "Copyright (C) 2018 Accelerated Designs. All rights reserved"))
      (libsource (lib "eagle-import") (part "PTS810SJG250SMTRLFS"))
    )
    (comp (ref "SW20")
      (value "PTS810SJG250SMTRLFS")
      (footprint "eagle-import:PTS810")
      (fields (field (name "COPYRIGHT") "Copyright (C) 2018 Accelerated Designs. All rights reserved"))
      (libsource (lib "eagle-import") (part "PTS810SJG250SMTRLFS"))
    )
    (comp (ref "U1")
      (value "NPN")
      (footprint "eagle-import:SOT323")
      (fields (field (name "PARTNO") "BC846BW_NPN"))
      (libsource (lib "eagle-import") (part "BC846BW"))
    )
    (comp (ref "U3")
      (value "NPN")
      (footprint "eagle-import:SOT323")
      (fields (field (name "PARTNO") "BC846BW_NPN"))
      (libsource (lib "eagle-import") (part "BC846BW"))
    )
    (comp (ref "U5")
      (value "NPN")
      (footprint "eagle-import:SOT323")
      (fields (field (name "PARTNO") "BC846BW_NPN"))
      (libsource (lib "eagle-import") (part "BC846BW"))
    )
    (comp (ref "U7")
      (value "NPN")
      (footprint "eagle-import:SOT323")
      (fields (field (name "PARTNO") "BC846BW_NPN"))
      (libsource (lib "eagle-import") (part "BC846BW"))
    )
    (comp (ref "U9")
      (value "NPN")
      (footprint "eagle-import:SOT323")
      (fields (field (name "PARTNO") "BC846BW_NPN"))
      (libsource (lib "eagle-import") (part "BC846BW"))
    )
    (comp (ref "U11")
      (value "NPN")
      (footprint "eagle-import:SOT323")
      (fields (field (name "PARTNO") "BC846BW_NPN"))
      (libsource (lib "eagle-import") (part "BC846BW"))
    )
    (comp (ref "U13")
      (value "NPN")
      (footprint "eagle-import:SOT323")
      (fields (field (name "PARTNO") "BC846BW_NPN"))
      (libsource (lib "eagle-import") (part "BC846BW"))
    )
    (comp (ref "U15")
      (value "NPN")
      (footprint "eagle-import:SOT323")
      (fields (field (name "PARTNO") "BC846BW_NPN"))
      (libsource (lib "eagle-import") (part "BC846BW"))
    )
    (comp (ref "U17")
      (value "NPN")
      (footprint "eagle-import:SOT323")
      (fields (field (name "PARTNO") "BC846BW_NPN"))
      (libsource (lib "eagle-import") (part "BC846BW"))
    )
    (comp (ref "U20")
      (value "NPN")
      (footprint "eagle-import:SOT323")
      (fields (field (name "PARTNO") "BC846BW_NPN"))
      (libsource (lib "eagle-import") (part "BC846BW"))
    )
  )
  (nets
    (net (code "1") (name "A_DIR+_A") (class "Default")
      (node (ref "J14") (pin "3") (pinfunction "3-DIR+_3") (pintype "passive"))
      (node (ref "R54") (pin "2") (pinfunction "2_2") (pintype "passive"))
    )
    (net (code "2") (name "A_DIR+_C") (class "Default")
      (node (ref "J18") (pin "3") (pinfunction "3-DIR+_3") (pintype "passive"))
      (node (ref "R70") (pin "2") (pinfunction "2_2") (pintype "passive"))
    )
    (net (code "3") (name "A_DIR+_WF") (class "Default")
      (node (ref "J4") (pin "3") (pinfunction "3-DIR+_3") (pintype "passive"))
      (node (ref "R14") (pin "2") (pinfunction "2_2") (pintype "passive"))
    )
    (net (code "4") (name "A_DIR+_X") (class "Default")
      (node (ref "J2") (pin "3") (pinfunction "3-DIR+_3") (pintype "passive"))
      (node (ref "R6") (pin "2") (pinfunction "2_2") (pintype "passive"))
    )
    (net (code "5") (name "A_DIR+_Y") (class "Default")
      (node (ref "J6") (pin "3") (pinfunction "3-DIR+_3") (pintype "passive"))
      (node (ref "R22") (pin "2") (pinfunction "2_2") (pintype "passive"))
    )
    (net (code "6") (name "A_DIR+_Z") (class "Default")
      (node (ref "J10") (pin "3") (pinfunction "3-DIR+_3") (pintype "passive"))
      (node (ref "R38") (pin "2") (pinfunction "2_2") (pintype "passive"))
    )
    (net (code "7") (name "A_DIR-A") (class "Default")
      (node (ref "J14") (pin "7") (pinfunction "7-DIR-_7") (pintype "passive"))
      (node (ref "LED54") (pin "2") (pinfunction "C_2") (pintype "passive"))
    )
    (net (code "8") (name "A_DIR-C") (class "Default")
      (node (ref "J18") (pin "7") (pinfunction "7-DIR-_7") (pintype "passive"))
      (node (ref "LED70") (pin "2") (pinfunction "C_2") (pintype "passive"))
    )
    (net (code "9") (name "A_DIR-X") (class "Default")
      (node (ref "J2") (pin "7") (pinfunction "7-DIR-_7") (pintype "passive"))
      (node (ref "LED6") (pin "2") (pinfunction "C_2") (pintype "passive"))
    )
    (net (code "10") (name "A_DIR-Y") (class "Default")
      (node (ref "J6") (pin "7") (pinfunction "7-DIR-_7") (pintype "passive"))
      (node (ref "LED22") (pin "2") (pinfunction "C_2") (pintype "passive"))
    )
    (net (code "11") (name "A_DIR-Z") (class "Default")
      (node (ref "J10") (pin "7") (pinfunction "7-DIR-_7") (pintype "passive"))
      (node (ref "LED38") (pin "2") (pinfunction "C_2") (pintype "passive"))
    )
    (net (code "12") (name "A_DIR-_WF") (class "Default")
      (node (ref "J4") (pin "7") (pinfunction "7-DIR-_7") (pintype "passive"))
      (node (ref "LED14") (pin "2") (pinfunction "C_2") (pintype "passive"))
    )
    (net (code "13") (name "A_ENABLE+_A") (class "Default")
      (node (ref "J14") (pin "4") (pinfunction "4-ENABLE+_4") (pintype "passive"))
      (node (ref "R55") (pin "2") (pinfunction "2_2") (pintype "passive"))
    )
    (net (code "14") (name "A_ENABLE+_C") (class "Default")
      (node (ref "J18") (pin "4") (pinfunction "4-ENABLE+_4") (pintype "passive"))
      (node (ref "R71") (pin "2") (pinfunction "2_2") (pintype "passive"))
    )
    (net (code "15") (name "A_ENABLE+_WF") (class "Default")
      (node (ref "J4") (pin "4") (pinfunction "4-ENABLE+_4") (pintype "passive"))
      (node (ref "R15") (pin "2") (pinfunction "2_2") (pintype "passive"))
    )
    (net (code "16") (name "A_ENABLE+_X") (class "Default")
      (node (ref "J2") (pin "4") (pinfunction "4-ENABLE+_4") (pintype "passive"))
      (node (ref "R7") (pin "2") (pinfunction "2_2") (pintype "passive"))
    )
    (net (code "17") (name "A_ENABLE+_Y") (class "Default")
      (node (ref "J6") (pin "4") (pinfunction "4-ENABLE+_4") (pintype "passive"))
      (node (ref "R23") (pin "2") (pinfunction "2_2") (pintype "passive"))
    )
    (net (code "18") (name "A_ENABLE+_Z") (class "Default")
      (node (ref "J10") (pin "4") (pinfunction "4-ENABLE+_4") (pintype "passive"))
      (node (ref "R39") (pin "2") (pinfunction "2_2") (pintype "passive"))
    )
    (net (code "19") (name "A_ENABLE-_A") (class "Default")
      (node (ref "J14") (pin "8") (pinfunction "8-ENABLE-_8") (pintype "passive"))
      (node (ref "LED55") (pin "2") (pinfunction "C_2") (pintype "passive"))
    )
    (net (code "20") (name "A_ENABLE-_C") (class "Default")
      (node (ref "J18") (pin "8") (pinfunction "8-ENABLE-_8") (pintype "passive"))
      (node (ref "LED71") (pin "2") (pinfunction "C_2") (pintype "passive"))
    )
    (net (code "21") (name "A_ENABLE-_WF") (class "Default")
      (node (ref "J4") (pin "8") (pinfunction "8-ENABLE-_8") (pintype "passive"))
      (node (ref "LED15") (pin "2") (pinfunction "C_2") (pintype "passive"))
    )
    (net (code "22") (name "A_ENABLE-_X") (class "Default")
      (node (ref "J2") (pin "8") (pinfunction "8-ENABLE-_8") (pintype "passive"))
      (node (ref "LED7") (pin "2") (pinfunction "C_2") (pintype "passive"))
    )
    (net (code "23") (name "A_ENABLE-_Y") (class "Default")
      (node (ref "J6") (pin "8") (pinfunction "8-ENABLE-_8") (pintype "passive"))
      (node (ref "LED23") (pin "2") (pinfunction "C_2") (pintype "passive"))
    )
    (net (code "24") (name "A_ENABLE-_Z") (class "Default")
      (node (ref "J10") (pin "8") (pinfunction "8-ENABLE-_8") (pintype "passive"))
      (node (ref "LED39") (pin "2") (pinfunction "C_2") (pintype "passive"))
    )
    (net (code "25") (name "A_HLFB+_A") (class "Default")
      (node (ref "J14") (pin "1") (pinfunction "1-HLFB+_1") (pintype "passive"))
      (node (ref "R56") (pin "2") (pinfunction "2_2") (pintype "passive"))
    )
    (net (code "26") (name "A_HLFB+_C") (class "Default")
      (node (ref "J18") (pin "1") (pinfunction "1-HLFB+_1") (pintype "passive"))
      (node (ref "R72") (pin "2") (pinfunction "2_2") (pintype "passive"))
    )
    (net (code "27") (name "A_HLFB+_WF") (class "Default")
      (node (ref "J4") (pin "1") (pinfunction "1-HLFB+_1") (pintype "passive"))
      (node (ref "R16") (pin "2") (pinfunction "2_2") (pintype "passive"))
    )
    (net (code "28") (name "A_HLFB+_X") (class "Default")
      (node (ref "J2") (pin "1") (pinfunction "1-HLFB+_1") (pintype "passive"))
      (node (ref "R8") (pin "2") (pinfunction "2_2") (pintype "passive"))
    )
    (net (code "29") (name "A_HLFB+_Y") (class "Default")
      (node (ref "J6") (pin "1") (pinfunction "1-HLFB+_1") (pintype "passive"))
      (node (ref "R24") (pin "2") (pinfunction "2_2") (pintype "passive"))
    )
    (net (code "30") (name "A_HLFB+_Z") (class "Default")
      (node (ref "J10") (pin "1") (pinfunction "1-HLFB+_1") (pintype "passive"))
      (node (ref "R40") (pin "2") (pinfunction "2_2") (pintype "passive"))
    )
    (net (code "31") (name "A_HLFB-_A") (class "Default")
      (node (ref "J14") (pin "5") (pinfunction "5-HLFB-_5") (pintype "passive"))
      (node (ref "LED56") (pin "2") (pinfunction "C_2") (pintype "passive"))
    )
    (net (code "32") (name "A_HLFB-_C") (class "Default")
      (node (ref "J18") (pin "5") (pinfunction "5-HLFB-_5") (pintype "passive"))
      (node (ref "LED72") (pin "2") (pinfunction "C_2") (pintype "passive"))
    )
    (net (code "33") (name "A_HLFB-_WF") (class "Default")
      (node (ref "J4") (pin "5") (pinfunction "5-HLFB-_5") (pintype "passive"))
      (node (ref "LED16") (pin "2") (pinfunction "C_2") (pintype "passive"))
    )
    (net (code "34") (name "A_HLFB-_X") (class "Default")
      (node (ref "J2") (pin "5") (pinfunction "5-HLFB-_5") (pintype "passive"))
      (node (ref "LED8") (pin "2") (pinfunction "C_2") (pintype "passive"))
    )
    (net (code "35") (name "A_HLFB-_Y") (class "Default")
      (node (ref "J6") (pin "5") (pinfunction "5-HLFB-_5") (pintype "passive"))
      (node (ref "LED24") (pin "2") (pinfunction "C_2") (pintype "passive"))
    )
    (net (code "36") (name "A_HLFB-_Z") (class "Default")
      (node (ref "J10") (pin "5") (pinfunction "5-HLFB-_5") (pintype "passive"))
      (node (ref "LED40") (pin "2") (pinfunction "C_2") (pintype "passive"))
    )
    (net (code "37") (name "A_STEP+_A") (class "Default")
      (node (ref "J14") (pin "2") (pinfunction "2-STEP+_2") (pintype "passive"))
      (node (ref "R53") (pin "2") (pinfunction "2_2") (pintype "passive"))
    )
    (net (code "38") (name "A_STEP+_C") (class "Default")
      (node (ref "J18") (pin "2") (pinfunction "2-STEP+_2") (pintype "passive"))
      (node (ref "R69") (pin "2") (pinfunction "2_2") (pintype "passive"))
    )
    (net (code "39") (name "A_STEP+_WF") (class "Default")
      (node (ref "J4") (pin "2") (pinfunction "2-STEP+_2") (pintype "passive"))
      (node (ref "R13") (pin "2") (pinfunction "2_2") (pintype "passive"))
    )
    (net (code "40") (name "A_STEP+_X") (class "Default")
      (node (ref "J2") (pin "2") (pinfunction "2-STEP+_2") (pintype "passive"))
      (node (ref "R5") (pin "2") (pinfunction "2_2") (pintype "passive"))
    )
    (net (code "41") (name "A_STEP+_Y") (class "Default")
      (node (ref "J6") (pin "2") (pinfunction "2-STEP+_2") (pintype "passive"))
      (node (ref "R21") (pin "2") (pinfunction "2_2") (pintype "passive"))
    )
    (net (code "42") (name "A_STEP+_Z") (class "Default")
      (node (ref "J10") (pin "2") (pinfunction "2-STEP+_2") (pintype "passive"))
      (node (ref "R37") (pin "2") (pinfunction "2_2") (pintype "passive"))
    )
    (net (code "43") (name "A_STEP-_A") (class "Default")
      (node (ref "J14") (pin "6") (pinfunction "6-STEP-_6") (pintype "passive"))
      (node (ref "LED53") (pin "2") (pinfunction "C_2") (pintype "passive"))
    )
    (net (code "44") (name "A_STEP-_C") (class "Default")
      (node (ref "J18") (pin "6") (pinfunction "6-STEP-_6") (pintype "passive"))
      (node (ref "LED69") (pin "2") (pinfunction "C_2") (pintype "passive"))
    )
    (net (code "45") (name "A_STEP-_WF") (class "Default")
      (node (ref "J4") (pin "6") (pinfunction "6-STEP-_6") (pintype "passive"))
      (node (ref "LED13") (pin "2") (pinfunction "C_2") (pintype "passive"))
    )
    (net (code "46") (name "A_STEP-_X") (class "Default")
      (node (ref "J2") (pin "6") (pinfunction "6-STEP-_6") (pintype "passive"))
      (node (ref "LED5") (pin "2") (pinfunction "C_2") (pintype "passive"))
    )
    (net (code "47") (name "A_STEP-_Y") (class "Default")
      (node (ref "J6") (pin "6") (pinfunction "6-STEP-_6") (pintype "passive"))
      (node (ref "LED21") (pin "2") (pinfunction "C_2") (pintype "passive"))
    )
    (net (code "48") (name "A_STEP-_Z") (class "Default")
      (node (ref "J10") (pin "6") (pinfunction "6-STEP-_6") (pintype "passive"))
      (node (ref "LED37") (pin "2") (pinfunction "C_2") (pintype "passive"))
    )
    (net (code "49") (name "BLACK_1") (class "Default")
      (node (ref "J11") (pin "2") (pinfunction "2_2") (pintype "passive"))
      (node (ref "J12") (pin "P$3") (pinfunction "P$3_P$3") (pintype "bidirectional"))
      (node (ref "R28") (pin "P$1") (pinfunction "1_P$1") (pintype "passive"))
      (node (ref "R29") (pin "P$1") (pinfunction "1_P$1") (pintype "passive"))
    )
    (net (code "50") (name "BLACK_2") (class "Default")
      (node (ref "J19") (pin "2") (pinfunction "2_2") (pintype "passive"))
      (node (ref "J20") (pin "P$3") (pinfunction "P$3_P$3") (pintype "bidirectional"))
      (node (ref "R42") (pin "P$1") (pinfunction "1_P$1") (pintype "passive"))
      (node (ref "R43") (pin "P$1") (pinfunction "1_P$1") (pintype "passive"))
    )
    (net (code "51") (name "BLACK_3") (class "Default")
      (node (ref "J23") (pin "2") (pinfunction "2_2") (pintype "passive"))
      (node (ref "J24") (pin "P$3") (pinfunction "P$3_P$3") (pintype "bidirectional"))
      (node (ref "R48") (pin "P$1") (pinfunction "1_P$1") (pintype "passive"))
      (node (ref "R57") (pin "P$1") (pinfunction "1_P$1") (pintype "passive"))
    )
    (net (code "52") (name "BLACK_4") (class "Default")
      (node (ref "J27") (pin "2") (pinfunction "2_2") (pintype "passive"))
      (node (ref "J28") (pin "P$3") (pinfunction "P$3_P$3") (pintype "bidirectional"))
      (node (ref "R63") (pin "P$1") (pinfunction "1_P$1") (pintype "passive"))
      (node (ref "R64") (pin "P$1") (pinfunction "1_P$1") (pintype "passive"))
    )
    (net (code "53") (name "BLACK_5") (class "Default")
      (node (ref "J31") (pin "2") (pinfunction "2_2") (pintype "passive"))
      (node (ref "J32") (pin "P$3") (pinfunction "P$3_P$3") (pintype "bidirectional"))
      (node (ref "R77") (pin "P$1") (pinfunction "1_P$1") (pintype "passive"))
      (node (ref "R78") (pin "P$1") (pinfunction "1_P$1") (pintype "passive"))
    )
    (net (code "54") (name "BLACK_6") (class "Default")
      (node (ref "J35") (pin "2") (pinfunction "2_2") (pintype "passive"))
      (node (ref "J36") (pin "P$3") (pinfunction "P$3_P$3") (pintype "bidirectional"))
      (node (ref "R83") (pin "P$1") (pinfunction "1_P$1") (pintype "passive"))
      (node (ref "R84") (pin "P$1") (pinfunction "1_P$1") (pintype "passive"))
    )
    (net (code "55") (name "BLACK_7") (class "Default")
      (node (ref "J39") (pin "2") (pinfunction "2_2") (pintype "passive"))
      (node (ref "J40") (pin "P$3") (pinfunction "P$3_P$3") (pintype "bidirectional"))
      (node (ref "R89") (pin "P$1") (pinfunction "1_P$1") (pintype "passive"))
      (node (ref "R90") (pin "P$1") (pinfunction "1_P$1") (pintype "passive"))
    )
    (net (code "56") (name "BLACK_8") (class "Default")
      (node (ref "J43") (pin "2") (pinfunction "2_2") (pintype "passive"))
      (node (ref "J44") (pin "P$3") (pinfunction "P$3_P$3") (pintype "bidirectional"))
      (node (ref "R95") (pin "P$1") (pinfunction "1_P$1") (pintype "passive"))
      (node (ref "R96") (pin "P$1") (pinfunction "1_P$1") (pintype "passive"))
    )
    (net (code "57") (name "BLACK_9") (class "Default")
      (node (ref "J47") (pin "2") (pinfunction "2_2") (pintype "passive"))
      (node (ref "J48") (pin "P$3") (pinfunction "P$3_P$3") (pintype "bidirectional"))
      (node (ref "R101") (pin "P$1") (pinfunction "1_P$1") (pintype "passive"))
      (node (ref "R102") (pin "P$1") (pinfunction "1_P$1") (pintype "passive"))
    )
    (net (code "58") (name "BLACK_E_STOP") (class "Default")
      (node (ref "J51") (pin "2") (pinfunction "2_2") (pintype "passive"))
      (node (ref "J52") (pin "P$3") (pinfunction "P$3_P$3") (pintype "bidirectional"))
      (node (ref "R107") (pin "P$1") (pinfunction "1_P$1") (pintype "passive"))
      (node (ref "R108") (pin "P$1") (pinfunction "1_P$1") (pintype "passive"))
    )
    (net (code "59") (name "BLUE") (class "Default")
      (node (ref "J11") (pin "1") (pinfunction "1_1") (pintype "passive"))
      (node (ref "J12") (pin "P$1") (pinfunction "P$1_P$1") (pintype "bidirectional"))
      (node (ref "J12") (pin "P$2") (pinfunction "P$2_P$2") (pintype "bidirectional"))
      (node (ref "J19") (pin "1") (pinfunction "1_1") (pintype "passive"))
      (node (ref "J20") (pin "P$1") (pinfunction "P$1_P$1") (pintype "bidirectional"))
      (node (ref "J20") (pin "P$2") (pinfunction "P$2_P$2") (pintype "bidirectional"))
      (node (ref "J23") (pin "1") (pinfunction "1_1") (pintype "passive"))
      (node (ref "J24") (pin "P$1") (pinfunction "P$1_P$1") (pintype "bidirectional"))
      (node (ref "J24") (pin "P$2") (pinfunction "P$2_P$2") (pintype "bidirectional"))
      (node (ref "J27") (pin "1") (pinfunction "1_1") (pintype "passive"))
      (node (ref "J28") (pin "P$1") (pinfunction "P$1_P$1") (pintype "bidirectional"))
      (node (ref "J28") (pin "P$2") (pinfunction "P$2_P$2") (pintype "bidirectional"))
      (node (ref "J31") (pin "1") (pinfunction "1_1") (pintype "passive"))
      (node (ref "J32") (pin "P$1") (pinfunction "P$1_P$1") (pintype "bidirectional"))
      (node (ref "J32") (pin "P$2") (pinfunction "P$2_P$2") (pintype "bidirectional"))
      (node (ref "J35") (pin "1") (pinfunction "1_1") (pintype "passive"))
      (node (ref "J36") (pin "P$1") (pinfunction "P$1_P$1") (pintype "bidirectional"))
      (node (ref "J36") (pin "P$2") (pinfunction "P$2_P$2") (pintype "bidirectional"))
      (node (ref "J39") (pin "1") (pinfunction "1_1") (pintype "passive"))
      (node (ref "J40") (pin "P$1") (pinfunction "P$1_P$1") (pintype "bidirectional"))
      (node (ref "J40") (pin "P$2") (pinfunction "P$2_P$2") (pintype "bidirectional"))
      (node (ref "J43") (pin "1") (pinfunction "1_1") (pintype "passive"))
      (node (ref "J44") (pin "P$1") (pinfunction "P$1_P$1") (pintype "bidirectional"))
      (node (ref "J44") (pin "P$2") (pinfunction "P$2_P$2") (pintype "bidirectional"))
      (node (ref "J47") (pin "1") (pinfunction "1_1") (pintype "passive"))
      (node (ref "J48") (pin "P$1") (pinfunction "P$1_P$1") (pintype "bidirectional"))
      (node (ref "J48") (pin "P$2") (pinfunction "P$2_P$2") (pintype "bidirectional"))
      (node (ref "J51") (pin "1") (pinfunction "1_1") (pintype "passive"))
      (node (ref "J52") (pin "P$1") (pinfunction "P$1_P$1") (pintype "bidirectional"))
      (node (ref "J52") (pin "P$2") (pinfunction "P$2_P$2") (pintype "bidirectional"))
      (node (ref "SW10") (pin "3") (pinfunction "3_3") (pintype "passive"))
      (node (ref "SW10") (pin "4") (pinfunction "4_4") (pintype "passive"))
      (node (ref "SW12") (pin "3") (pinfunction "3_3") (pintype "passive"))
      (node (ref "SW12") (pin "4") (pinfunction "4_4") (pintype "passive"))
      (node (ref "SW14") (pin "3") (pinfunction "3_3") (pintype "passive"))
      (node (ref "SW14") (pin "4") (pinfunction "4_4") (pintype "passive"))
      (node (ref "SW16") (pin "3") (pinfunction "3_3") (pintype "passive"))
      (node (ref "SW16") (pin "4") (pinfunction "4_4") (pintype "passive"))
      (node (ref "SW18") (pin "3") (pinfunction "3_3") (pintype "passive"))
      (node (ref "SW18") (pin "4") (pinfunction "4_4") (pintype "passive"))
      (node (ref "SW2") (pin "3") (pinfunction "3_3") (pintype "passive"))
      (node (ref "SW2") (pin "4") (pinfunction "4_4") (pintype "passive"))
      (node (ref "SW20") (pin "3") (pinfunction "3_3") (pintype "passive"))
      (node (ref "SW20") (pin "4") (pinfunction "4_4") (pintype "passive"))
      (node (ref "SW4") (pin "3") (pinfunction "3_3") (pintype "passive"))
      (node (ref "SW4") (pin "4") (pinfunction "4_4") (pintype "passive"))
      (node (ref "SW6") (pin "3") (pinfunction "3_3") (pintype "passive"))
      (node (ref "SW6") (pin "4") (pinfunction "4_4") (pintype "passive"))
      (node (ref "SW8") (pin "3") (pinfunction "3_3") (pintype "passive"))
      (node (ref "SW8") (pin "4") (pinfunction "4_4") (pintype "passive"))
    )
    (net (code "60") (name "BROWN") (class "Default")
      (node (ref "J11") (pin "3") (pinfunction "3_3") (pintype "passive"))
      (node (ref "J12") (pin "P$4") (pinfunction "P$4_P$4") (pintype "bidirectional"))
      (node (ref "J19") (pin "3") (pinfunction "3_3") (pintype "passive"))
      (node (ref "J20") (pin "P$4") (pinfunction "P$4_P$4") (pintype "bidirectional"))
      (node (ref "J23") (pin "3") (pinfunction "3_3") (pintype "passive"))
      (node (ref "J24") (pin "P$4") (pinfunction "P$4_P$4") (pintype "bidirectional"))
      (node (ref "J27") (pin "3") (pinfunction "3_3") (pintype "passive"))
      (node (ref "J28") (pin "P$4") (pinfunction "P$4_P$4") (pintype "bidirectional"))
      (node (ref "J31") (pin "3") (pinfunction "3_3") (pintype "passive"))
      (node (ref "J32") (pin "P$4") (pinfunction "P$4_P$4") (pintype "bidirectional"))
      (node (ref "J35") (pin "3") (pinfunction "3_3") (pintype "passive"))
      (node (ref "J36") (pin "P$4") (pinfunction "P$4_P$4") (pintype "bidirectional"))
      (node (ref "J39") (pin "3") (pinfunction "3_3") (pintype "passive"))
      (node (ref "J40") (pin "P$4") (pinfunction "P$4_P$4") (pintype "bidirectional"))
      (node (ref "J43") (pin "3") (pinfunction "3_3") (pintype "passive"))
      (node (ref "J44") (pin "P$4") (pinfunction "P$4_P$4") (pintype "bidirectional"))
      (node (ref "J47") (pin "3") (pinfunction "3_3") (pintype "passive"))
      (node (ref "J48") (pin "P$4") (pinfunction "P$4_P$4") (pintype "bidirectional"))
      (node (ref "J51") (pin "3") (pinfunction "3_3") (pintype "passive"))
      (node (ref "J52") (pin "P$4") (pinfunction "P$4_P$4") (pintype "bidirectional"))
      (node (ref "R100") (pin "P$1") (pinfunction "1_P$1") (pintype "passive"))
      (node (ref "R106") (pin "P$1") (pinfunction "1_P$1") (pintype "passive"))
      (node (ref "R27") (pin "P$1") (pinfunction "1_P$1") (pintype "passive"))
      (node (ref "R41") (pin "P$1") (pinfunction "1_P$1") (pintype "passive"))
      (node (ref "R47") (pin "P$1") (pinfunction "1_P$1") (pintype "passive"))
      (node (ref "R62") (pin "P$1") (pinfunction "1_P$1") (pintype "passive"))
      (node (ref "R76") (pin "P$1") (pinfunction "1_P$1") (pintype "passive"))
      (node (ref "R82") (pin "P$1") (pinfunction "1_P$1") (pintype "passive"))
      (node (ref "R88") (pin "P$1") (pinfunction "1_P$1") (pintype "passive"))
      (node (ref "R94") (pin "P$1") (pinfunction "1_P$1") (pintype "passive"))
      (node (ref "U1") (pin "3") (pinfunction "C(3)_3") (pintype "input"))
      (node (ref "U11") (pin "3") (pinfunction "C(3)_3") (pintype "input"))
      (node (ref "U13") (pin "3") (pinfunction "C(3)_3") (pintype "input"))
      (node (ref "U15") (pin "3") (pinfunction "C(3)_3") (pintype "input"))
      (node (ref "U17") (pin "3") (pinfunction "C(3)_3") (pintype "input"))
      (node (ref "U20") (pin "3") (pinfunction "C(3)_3") (pintype "input"))
      (node (ref "U3") (pin "3") (pinfunction "C(3)_3") (pintype "input"))
      (node (ref "U5") (pin "3") (pinfunction "C(3)_3") (pintype "input"))
      (node (ref "U7") (pin "3") (pinfunction "C(3)_3") (pintype "input"))
      (node (ref "U9") (pin "3") (pinfunction "C(3)_3") (pintype "input"))
    )
    (net (code "61") (name "B_DIR+_A") (class "Default")
      (node (ref "J13") (pin "3") (pinfunction "3-DIR+_3") (pintype "passive"))
      (node (ref "R50") (pin "2") (pinfunction "2_2") (pintype "passive"))
    )
    (net (code "62") (name "B_DIR+_C") (class "Default")
      (node (ref "J1") (pin "3") (pinfunction "3-DIR+_3") (pintype "passive"))
      (node (ref "R2") (pin "2") (pinfunction "2_2") (pintype "passive"))
    )
    (net (code "63") (name "B_DIR+_WF") (class "Default")
      (node (ref "J17") (pin "3") (pinfunction "3-DIR+_3") (pintype "passive"))
      (node (ref "R66") (pin "2") (pinfunction "2_2") (pintype "passive"))
    )
    (net (code "64") (name "B_DIR+_X") (class "Default")
      (node (ref "J3") (pin "3") (pinfunction "3-DIR+_3") (pintype "passive"))
      (node (ref "R10") (pin "2") (pinfunction "2_2") (pintype "passive"))
    )
    (net (code "65") (name "B_DIR+_Y") (class "Default")
      (node (ref "J5") (pin "3") (pinfunction "3-DIR+_3") (pintype "passive"))
      (node (ref "R18") (pin "2") (pinfunction "2_2") (pintype "passive"))
    )
    (net (code "66") (name "B_DIR+_Z") (class "Default")
      (node (ref "J9") (pin "3") (pinfunction "3-DIR+_3") (pintype "passive"))
      (node (ref "R34") (pin "2") (pinfunction "2_2") (pintype "passive"))
    )
    (net (code "67") (name "B_DIR-C") (class "Default")
      (node (ref "J1") (pin "7") (pinfunction "7-DIR-_7") (pintype "passive"))
      (node (ref "LED2") (pin "2") (pinfunction "C_2") (pintype "passive"))
    )
    (net (code "68") (name "B_DIR-X") (class "Default")
      (node (ref "J3") (pin "7") (pinfunction "7-DIR-_7") (pintype "passive"))
      (node (ref "LED10") (pin "2") (pinfunction "C_2") (pintype "passive"))
    )
    (net (code "69") (name "B_DIR-Y") (class "Default")
      (node (ref "J5") (pin "7") (pinfunction "7-DIR-_7") (pintype "passive"))
      (node (ref "LED18") (pin "2") (pinfunction "C_2") (pintype "passive"))
    )
    (net (code "70") (name "B_DIR-Z") (class "Default")
      (node (ref "J9") (pin "7") (pinfunction "7-DIR-_7") (pintype "passive"))
      (node (ref "LED34") (pin "2") (pinfunction "C_2") (pintype "passive"))
    )
    (net (code "71") (name "B_DIR-_A") (class "Default")
      (node (ref "J13") (pin "7") (pinfunction "7-DIR-_7") (pintype "passive"))
      (node (ref "LED50") (pin "2") (pinfunction "C_2") (pintype "passive"))
    )
    (net (code "72") (name "B_DIR-_WF") (class "Default")
      (node (ref "J17") (pin "7") (pinfunction "7-DIR-_7") (pintype "passive"))
      (node (ref "LED66") (pin "2") (pinfunction "C_2") (pintype "passive"))
    )
    (net (code "73") (name "B_ENABLE+_A") (class "Default")
      (node (ref "J13") (pin "4") (pinfunction "4-ENABLE+_4") (pintype "passive"))
      (node (ref "R51") (pin "2") (pinfunction "2_2") (pintype "passive"))
    )
    (net (code "74") (name "B_ENABLE+_C") (class "Default")
      (node (ref "J1") (pin "4") (pinfunction "4-ENABLE+_4") (pintype "passive"))
      (node (ref "R3") (pin "2") (pinfunction "2_2") (pintype "passive"))
    )
    (net (code "75") (name "B_ENABLE+_WF") (class "Default")
      (node (ref "J17") (pin "4") (pinfunction "4-ENABLE+_4") (pintype "passive"))
      (node (ref "R67") (pin "2") (pinfunction "2_2") (pintype "passive"))
    )
    (net (code "76") (name "B_ENABLE+_X") (class "Default")
      (node (ref "J3") (pin "4") (pinfunction "4-ENABLE+_4") (pintype "passive"))
      (node (ref "R11") (pin "2") (pinfunction "2_2") (pintype "passive"))
    )
    (net (code "77") (name "B_ENABLE+_Y") (class "Default")
      (node (ref "J5") (pin "4") (pinfunction "4-ENABLE+_4") (pintype "passive"))
      (node (ref "R19") (pin "2") (pinfunction "2_2") (pintype "passive"))
    )
    (net (code "78") (name "B_ENABLE+_Z") (class "Default")
      (node (ref "J9") (pin "4") (pinfunction "4-ENABLE+_4") (pintype "passive"))
      (node (ref "R35") (pin "2") (pinfunction "2_2") (pintype "passive"))
    )
    (net (code "79") (name "B_ENABLE-_A") (class "Default")
      (node (ref "J13") (pin "8") (pinfunction "8-ENABLE-_8") (pintype "passive"))
      (node (ref "LED51") (pin "2") (pinfunction "C_2") (pintype "passive"))
    )
    (net (code "80") (name "B_ENABLE-_C") (class "Default")
      (node (ref "J1") (pin "8") (pinfunction "8-ENABLE-_8") (pintype "passive"))
      (node (ref "LED3") (pin "2") (pinfunction "C_2") (pintype "passive"))
    )
    (net (code "81") (name "B_ENABLE-_WF") (class "Default")
      (node (ref "J17") (pin "8") (pinfunction "8-ENABLE-_8") (pintype "passive"))
      (node (ref "LED67") (pin "2") (pinfunction "C_2") (pintype "passive"))
    )
    (net (code "82") (name "B_ENABLE-_X") (class "Default")
      (node (ref "J3") (pin "8") (pinfunction "8-ENABLE-_8") (pintype "passive"))
      (node (ref "LED11") (pin "2") (pinfunction "C_2") (pintype "passive"))
    )
    (net (code "83") (name "B_ENABLE-_Y") (class "Default")
      (node (ref "J5") (pin "8") (pinfunction "8-ENABLE-_8") (pintype "passive"))
      (node (ref "LED19") (pin "2") (pinfunction "C_2") (pintype "passive"))
    )
    (net (code "84") (name "B_ENABLE-_Z") (class "Default")
      (node (ref "J9") (pin "8") (pinfunction "8-ENABLE-_8") (pintype "passive"))
      (node (ref "LED35") (pin "2") (pinfunction "C_2") (pintype "passive"))
    )
    (net (code "85") (name "B_HLFB+_A") (class "Default")
      (node (ref "J13") (pin "1") (pinfunction "1-HLFB+_1") (pintype "passive"))
      (node (ref "R52") (pin "2") (pinfunction "2_2") (pintype "passive"))
    )
    (net (code "86") (name "B_HLFB+_C") (class "Default")
      (node (ref "J1") (pin "1") (pinfunction "1-HLFB+_1") (pintype "passive"))
      (node (ref "R4") (pin "2") (pinfunction "2_2") (pintype "passive"))
    )
    (net (code "87") (name "B_HLFB+_WF") (class "Default")
      (node (ref "J17") (pin "1") (pinfunction "1-HLFB+_1") (pintype "passive"))
      (node (ref "R68") (pin "2") (pinfunction "2_2") (pintype "passive"))
    )
    (net (code "88") (name "B_HLFB+_X") (class "Default")
      (node (ref "J3") (pin "1") (pinfunction "1-HLFB+_1") (pintype "passive"))
      (node (ref "R12") (pin "2") (pinfunction "2_2") (pintype "passive"))
    )
    (net (code "89") (name "B_HLFB+_Y") (class "Default")
      (node (ref "J5") (pin "1") (pinfunction "1-HLFB+_1") (pintype "passive"))
      (node (ref "R20") (pin "2") (pinfunction "2_2") (pintype "passive"))
    )
    (net (code "90") (name "B_HLFB+_Z") (class "Default")
      (node (ref "J9") (pin "1") (pinfunction "1-HLFB+_1") (pintype "passive"))
      (node (ref "R36") (pin "2") (pinfunction "2_2") (pintype "passive"))
    )
    (net (code "91") (name "B_HLFB-_A") (class "Default")
      (node (ref "J13") (pin "5") (pinfunction "5-HLFB-_5") (pintype "passive"))
      (node (ref "LED52") (pin "2") (pinfunction "C_2") (pintype "passive"))
    )
    (net (code "92") (name "B_HLFB-_C") (class "Default")
      (node (ref "J1") (pin "5") (pinfunction "5-HLFB-_5") (pintype "passive"))
      (node (ref "LED4") (pin "2") (pinfunction "C_2") (pintype "passive"))
    )
    (net (code "93") (name "B_HLFB-_WF") (class "Default")
      (node (ref "J17") (pin "5") (pinfunction "5-HLFB-_5") (pintype "passive"))
      (node (ref "LED68") (pin "2") (pinfunction "C_2") (pintype "passive"))
    )
    (net (code "94") (name "B_HLFB-_X") (class "Default")
      (node (ref "J3") (pin "5") (pinfunction "5-HLFB-_5") (pintype "passive"))
      (node (ref "LED12") (pin "2") (pinfunction "C_2") (pintype "passive"))
    )
    (net (code "95") (name "B_HLFB-_Y") (class "Default")
      (node (ref "J5") (pin "5") (pinfunction "5-HLFB-_5") (pintype "passive"))
      (node (ref "LED20") (pin "2") (pinfunction "C_2") (pintype "passive"))
    )
    (net (code "96") (name "B_HLFB-_Z") (class "Default")
      (node (ref "J9") (pin "5") (pinfunction "5-HLFB-_5") (pintype "passive"))
      (node (ref "LED36") (pin "2") (pinfunction "C_2") (pintype "passive"))
    )
    (net (code "97") (name "B_STEP+_A") (class "Default")
      (node (ref "J13") (pin "2") (pinfunction "2-STEP+_2") (pintype "passive"))
      (node (ref "R49") (pin "2") (pinfunction "2_2") (pintype "passive"))
    )
    (net (code "98") (name "B_STEP+_C") (class "Default")
      (node (ref "J1") (pin "2") (pinfunction "2-STEP+_2") (pintype "passive"))
      (node (ref "R1") (pin "2") (pinfunction "2_2") (pintype "passive"))
    )
    (net (code "99") (name "B_STEP+_WF") (class "Default")
      (node (ref "J17") (pin "2") (pinfunction "2-STEP+_2") (pintype "passive"))
      (node (ref "R65") (pin "2") (pinfunction "2_2") (pintype "passive"))
    )
    (net (code "100") (name "B_STEP+_X") (class "Default")
      (node (ref "J3") (pin "2") (pinfunction "2-STEP+_2") (pintype "passive"))
      (node (ref "R9") (pin "2") (pinfunction "2_2") (pintype "passive"))
    )
    (net (code "101") (name "B_STEP+_Y") (class "Default")
      (node (ref "J5") (pin "2") (pinfunction "2-STEP+_2") (pintype "passive"))
      (node (ref "R17") (pin "2") (pinfunction "2_2") (pintype "passive"))
    )
    (net (code "102") (name "B_STEP+_Z") (class "Default")
      (node (ref "J9") (pin "2") (pinfunction "2-STEP+_2") (pintype "passive"))
      (node (ref "R33") (pin "2") (pinfunction "2_2") (pintype "passive"))
    )
    (net (code "103") (name "B_STEP-_A") (class "Default")
      (node (ref "J13") (pin "6") (pinfunction "6-STEP-_6") (pintype "passive"))
      (node (ref "LED49") (pin "2") (pinfunction "C_2") (pintype "passive"))
    )
    (net (code "104") (name "B_STEP-_C") (class "Default")
      (node (ref "J1") (pin "6") (pinfunction "6-STEP-_6") (pintype "passive"))
      (node (ref "LED1") (pin "2") (pinfunction "C_2") (pintype "passive"))
    )
    (net (code "105") (name "B_STEP-_WF") (class "Default")
      (node (ref "J17") (pin "6") (pinfunction "6-STEP-_6") (pintype "passive"))
      (node (ref "LED65") (pin "2") (pinfunction "C_2") (pintype "passive"))
    )
    (net (code "106") (name "B_STEP-_X") (class "Default")
      (node (ref "J3") (pin "6") (pinfunction "6-STEP-_6") (pintype "passive"))
      (node (ref "LED9") (pin "2") (pinfunction "C_2") (pintype "passive"))
    )
    (net (code "107") (name "B_STEP-_Y") (class "Default")
      (node (ref "J5") (pin "6") (pinfunction "6-STEP-_6") (pintype "passive"))
      (node (ref "LED17") (pin "2") (pinfunction "C_2") (pintype "passive"))
    )
    (net (code "108") (name "B_STEP-_Z") (class "Default")
      (node (ref "J9") (pin "6") (pinfunction "6-STEP-_6") (pintype "passive"))
      (node (ref "LED33") (pin "2") (pinfunction "C_2") (pintype "passive"))
    )
    (net (code "109") (name "Net-(LED1-A)") (class "Default")
      (node (ref "LED1") (pin "1") (pinfunction "A_1") (pintype "passive"))
      (node (ref "R1") (pin "1") (pinfunction "1_1") (pintype "passive"))
    )
    (net (code "110") (name "Net-(LED2-A)") (class "Default")
      (node (ref "LED2") (pin "1") (pinfunction "A_1") (pintype "passive"))
      (node (ref "R2") (pin "1") (pinfunction "1_1") (pintype "passive"))
    )
    (net (code "111") (name "Net-(LED3-A)") (class "Default")
      (node (ref "LED3") (pin "1") (pinfunction "A_1") (pintype "passive"))
      (node (ref "R3") (pin "1") (pinfunction "1_1") (pintype "passive"))
    )
    (net (code "112") (name "Net-(LED4-A)") (class "Default")
      (node (ref "LED4") (pin "1") (pinfunction "A_1") (pintype "passive"))
      (node (ref "R4") (pin "1") (pinfunction "1_1") (pintype "passive"))
    )
    (net (code "113") (name "Net-(LED5-A)") (class "Default")
      (node (ref "LED5") (pin "1") (pinfunction "A_1") (pintype "passive"))
      (node (ref "R5") (pin "1") (pinfunction "1_1") (pintype "passive"))
    )
    (net (code "114") (name "Net-(LED6-A)") (class "Default")
      (node (ref "LED6") (pin "1") (pinfunction "A_1") (pintype "passive"))
      (node (ref "R6") (pin "1") (pinfunction "1_1") (pintype "passive"))
    )
    (net (code "115") (name "Net-(LED7-A)") (class "Default")
      (node (ref "LED7") (pin "1") (pinfunction "A_1") (pintype "passive"))
      (node (ref "R7") (pin "1") (pinfunction "1_1") (pintype "passive"))
    )
    (net (code "116") (name "Net-(LED8-A)") (class "Default")
      (node (ref "LED8") (pin "1") (pinfunction "A_1") (pintype "passive"))
      (node (ref "R8") (pin "1") (pinfunction "1_1") (pintype "passive"))
    )
    (net (code "117") (name "Net-(LED9-A)") (class "Default")
      (node (ref "LED9") (pin "1") (pinfunction "A_1") (pintype "passive"))
      (node (ref "R9") (pin "1") (pinfunction "1_1") (pintype "passive"))
    )
    (net (code "118") (name "Net-(LED10-A)") (class "Default")
      (node (ref "LED10") (pin "1") (pinfunction "A_1") (pintype "passive"))
      (node (ref "R10") (pin "1") (pinfunction "1_1") (pintype "passive"))
    )
    (net (code "119") (name "Net-(LED11-A)") (class "Default")
      (node (ref "LED11") (pin "1") (pinfunction "A_1") (pintype "passive"))
      (node (ref "R11") (pin "1") (pinfunction "1_1") (pintype "passive"))
    )
    (net (code "120") (name "Net-(LED12-A)") (class "Default")
      (node (ref "LED12") (pin "1") (pinfunction "A_1") (pintype "passive"))
      (node (ref "R12") (pin "1") (pinfunction "1_1") (pintype "passive"))
    )
    (net (code "121") (name "Net-(LED13-A)") (class "Default")
      (node (ref "LED13") (pin "1") (pinfunction "A_1") (pintype "passive"))
      (node (ref "R13") (pin "1") (pinfunction "1_1") (pintype "passive"))
    )
    (net (code "122") (name "Net-(LED14-A)") (class "Default")
      (node (ref "LED14") (pin "1") (pinfunction "A_1") (pintype "passive"))
      (node (ref "R14") (pin "1") (pinfunction "1_1") (pintype "passive"))
    )
    (net (code "123") (name "Net-(LED15-A)") (class "Default")
      (node (ref "LED15") (pin "1") (pinfunction "A_1") (pintype "passive"))
      (node (ref "R15") (pin "1") (pinfunction "1_1") (pintype "passive"))
    )
    (net (code "124") (name "Net-(LED16-A)") (class "Default")
      (node (ref "LED16") (pin "1") (pinfunction "A_1") (pintype "passive"))
      (node (ref "R16") (pin "1") (pinfunction "1_1") (pintype "passive"))
    )
    (net (code "125") (name "Net-(LED17-A)") (class "Default")
      (node (ref "LED17") (pin "1") (pinfunction "A_1") (pintype "passive"))
      (node (ref "R17") (pin "1") (pinfunction "1_1") (pintype "passive"))
    )
    (net (code "126") (name "Net-(LED18-A)") (class "Default")
      (node (ref "LED18") (pin "1") (pinfunction "A_1") (pintype "passive"))
      (node (ref "R18") (pin "1") (pinfunction "1_1") (pintype "passive"))
    )
    (net (code "127") (name "Net-(LED19-A)") (class "Default")
      (node (ref "LED19") (pin "1") (pinfunction "A_1") (pintype "passive"))
      (node (ref "R19") (pin "1") (pinfunction "1_1") (pintype "passive"))
    )
    (net (code "128") (name "Net-(LED20-A)") (class "Default")
      (node (ref "LED20") (pin "1") (pinfunction "A_1") (pintype "passive"))
      (node (ref "R20") (pin "1") (pinfunction "1_1") (pintype "passive"))
    )
    (net (code "129") (name "Net-(LED21-A)") (class "Default")
      (node (ref "LED21") (pin "1") (pinfunction "A_1") (pintype "passive"))
      (node (ref "R21") (pin "1") (pinfunction "1_1") (pintype "passive"))
    )
    (net (code "130") (name "Net-(LED22-A)") (class "Default")
      (node (ref "LED22") (pin "1") (pinfunction "A_1") (pintype "passive"))
      (node (ref "R22") (pin "1") (pinfunction "1_1") (pintype "passive"))
    )
    (net (code "131") (name "Net-(LED23-A)") (class "Default")
      (node (ref "LED23") (pin "1") (pinfunction "A_1") (pintype "passive"))
      (node (ref "R23") (pin "1") (pinfunction "1_1") (pintype "passive"))
    )
    (net (code "132") (name "Net-(LED24-A)") (class "Default")
      (node (ref "LED24") (pin "1") (pinfunction "A_1") (pintype "passive"))
      (node (ref "R24") (pin "1") (pinfunction "1_1") (pintype "passive"))
    )
    (net (code "133") (name "Net-(LED25-A)") (class "Default")
      (node (ref "LED25") (pin "1") (pinfunction "A_1") (pintype "passive"))
      (node (ref "R27") (pin "P$2") (pinfunction "2_P$2") (pintype "passive"))
      (node (ref "U1") (pin "1") (pinfunction "B(2)_1") (pintype "input"))
    )
    (net (code "134") (name "Net-(LED25-C)") (class "Default")
      (node (ref "LED25") (pin "2") (pinfunction "C_2") (pintype "passive"))
      (node (ref "R29") (pin "P$2") (pinfunction "2_P$2") (pintype "passive"))
      (node (ref "SW2") (pin "1") (pinfunction "1_1") (pintype "passive"))
      (node (ref "SW2") (pin "2") (pinfunction "2_2") (pintype "passive"))
    )
    (net (code "135") (name "Net-(LED28-A)") (class "Default")
      (node (ref "LED28") (pin "1") (pinfunction "A_1") (pintype "passive"))
      (node (ref "R41") (pin "P$2") (pinfunction "2_P$2") (pintype "passive"))
      (node (ref "U3") (pin "1") (pinfunction "B(2)_1") (pintype "input"))
    )
    (net (code "136") (name "Net-(LED28-C)") (class "Default")
      (node (ref "LED28") (pin "2") (pinfunction "C_2") (pintype "passive"))
      (node (ref "R43") (pin "P$2") (pinfunction "2_P$2") (pintype "passive"))
      (node (ref "SW4") (pin "1") (pinfunction "1_1") (pintype "passive"))
      (node (ref "SW4") (pin "2") (pinfunction "2_2") (pintype "passive"))
    )
    (net (code "137") (name "Net-(LED30-A)") (class "Default")
      (node (ref "LED30") (pin "1") (pinfunction "A_1") (pintype "passive"))
      (node (ref "R47") (pin "P$2") (pinfunction "2_P$2") (pintype "passive"))
      (node (ref "U5") (pin "1") (pinfunction "B(2)_1") (pintype "input"))
    )
    (net (code "138") (name "Net-(LED30-C)") (class "Default")
      (node (ref "LED30") (pin "2") (pinfunction "C_2") (pintype "passive"))
      (node (ref "R57") (pin "P$2") (pinfunction "2_P$2") (pintype "passive"))
      (node (ref "SW6") (pin "1") (pinfunction "1_1") (pintype "passive"))
      (node (ref "SW6") (pin "2") (pinfunction "2_2") (pintype "passive"))
    )
    (net (code "139") (name "Net-(LED32-A)") (class "Default")
      (node (ref "LED32") (pin "1") (pinfunction "A_1") (pintype "passive"))
      (node (ref "R62") (pin "P$2") (pinfunction "2_P$2") (pintype "passive"))
      (node (ref "U7") (pin "1") (pinfunction "B(2)_1") (pintype "input"))
    )
    (net (code "140") (name "Net-(LED32-C)") (class "Default")
      (node (ref "LED32") (pin "2") (pinfunction "C_2") (pintype "passive"))
      (node (ref "R64") (pin "P$2") (pinfunction "2_P$2") (pintype "passive"))
      (node (ref "SW8") (pin "1") (pinfunction "1_1") (pintype "passive"))
      (node (ref "SW8") (pin "2") (pinfunction "2_2") (pintype "passive"))
    )
    (net (code "141") (name "Net-(LED33-A)") (class "Default")
      (node (ref "LED33") (pin "1") (pinfunction "A_1") (pintype "passive"))
      (node (ref "R33") (pin "1") (pinfunction "1_1") (pintype "passive"))
    )
    (net (code "142") (name "Net-(LED34-A)") (class "Default")
      (node (ref "LED34") (pin "1") (pinfunction "A_1") (pintype "passive"))
      (node (ref "R34") (pin "1") (pinfunction "1_1") (pintype "passive"))
    )
    (net (code "143") (name "Net-(LED35-A)") (class "Default")
      (node (ref "LED35") (pin "1") (pinfunction "A_1") (pintype "passive"))
      (node (ref "R35") (pin "1") (pinfunction "1_1") (pintype "passive"))
    )
    (net (code "144") (name "Net-(LED36-A)") (class "Default")
      (node (ref "LED36") (pin "1") (pinfunction "A_1") (pintype "passive"))
      (node (ref "R36") (pin "1") (pinfunction "1_1") (pintype "passive"))
    )
    (net (code "145") (name "Net-(LED37-A)") (class "Default")
      (node (ref "LED37") (pin "1") (pinfunction "A_1") (pintype "passive"))
      (node (ref "R37") (pin "1") (pinfunction "1_1") (pintype "passive"))
    )
    (net (code "146") (name "Net-(LED38-A)") (class "Default")
      (node (ref "LED38") (pin "1") (pinfunction "A_1") (pintype "passive"))
      (node (ref "R38") (pin "1") (pinfunction "1_1") (pintype "passive"))
    )
    (net (code "147") (name "Net-(LED39-A)") (class "Default")
      (node (ref "LED39") (pin "1") (pinfunction "A_1") (pintype "passive"))
      (node (ref "R39") (pin "1") (pinfunction "1_1") (pintype "passive"))
    )
    (net (code "148") (name "Net-(LED40-A)") (class "Default")
      (node (ref "LED40") (pin "1") (pinfunction "A_1") (pintype "passive"))
      (node (ref "R40") (pin "1") (pinfunction "1_1") (pintype "passive"))
    )
    (net (code "149") (name "Net-(LED42-A)") (class "Default")
      (node (ref "LED42") (pin "1") (pinfunction "A_1") (pintype "passive"))
      (node (ref "R76") (pin "P$2") (pinfunction "2_P$2") (pintype "passive"))
      (node (ref "U9") (pin "1") (pinfunction "B(2)_1") (pintype "input"))
    )
    (net (code "150") (name "Net-(LED42-C)") (class "Default")
      (node (ref "LED42") (pin "2") (pinfunction "C_2") (pintype "passive"))
      (node (ref "R78") (pin "P$2") (pinfunction "2_P$2") (pintype "passive"))
      (node (ref "SW10") (pin "1") (pinfunction "1_1") (pintype "passive"))
      (node (ref "SW10") (pin "2") (pinfunction "2_2") (pintype "passive"))
    )
    (net (code "151") (name "Net-(LED44-A)") (class "Default")
      (node (ref "LED44") (pin "1") (pinfunction "A_1") (pintype "passive"))
      (node (ref "R82") (pin "P$2") (pinfunction "2_P$2") (pintype "passive"))
      (node (ref "U11") (pin "1") (pinfunction "B(2)_1") (pintype "input"))
    )
    (net (code "152") (name "Net-(LED44-C)") (class "Default")
      (node (ref "LED44") (pin "2") (pinfunction "C_2") (pintype "passive"))
      (node (ref "R84") (pin "P$2") (pinfunction "2_P$2") (pintype "passive"))
      (node (ref "SW12") (pin "1") (pinfunction "1_1") (pintype "passive"))
      (node (ref "SW12") (pin "2") (pinfunction "2_2") (pintype "passive"))
    )
    (net (code "153") (name "Net-(LED46-A)") (class "Default")
      (node (ref "LED46") (pin "1") (pinfunction "A_1") (pintype "passive"))
      (node (ref "R88") (pin "P$2") (pinfunction "2_P$2") (pintype "passive"))
      (node (ref "U13") (pin "1") (pinfunction "B(2)_1") (pintype "input"))
    )
    (net (code "154") (name "Net-(LED46-C)") (class "Default")
      (node (ref "LED46") (pin "2") (pinfunction "C_2") (pintype "passive"))
      (node (ref "R90") (pin "P$2") (pinfunction "2_P$2") (pintype "passive"))
      (node (ref "SW14") (pin "1") (pinfunction "1_1") (pintype "passive"))
      (node (ref "SW14") (pin "2") (pinfunction "2_2") (pintype "passive"))
    )
    (net (code "155") (name "Net-(LED48-A)") (class "Default")
      (node (ref "LED48") (pin "1") (pinfunction "A_1") (pintype "passive"))
      (node (ref "R94") (pin "P$2") (pinfunction "2_P$2") (pintype "passive"))
      (node (ref "U15") (pin "1") (pinfunction "B(2)_1") (pintype "input"))
    )
    (net (code "156") (name "Net-(LED48-C)") (class "Default")
      (node (ref "LED48") (pin "2") (pinfunction "C_2") (pintype "passive"))
      (node (ref "R96") (pin "P$2") (pinfunction "2_P$2") (pintype "passive"))
      (node (ref "SW16") (pin "1") (pinfunction "1_1") (pintype "passive"))
      (node (ref "SW16") (pin "2") (pinfunction "2_2") (pintype "passive"))
    )
    (net (code "157") (name "Net-(LED49-A)") (class "Default")
      (node (ref "LED49") (pin "1") (pinfunction "A_1") (pintype "passive"))
      (node (ref "R49") (pin "1") (pinfunction "1_1") (pintype "passive"))
    )
    (net (code "158") (name "Net-(LED50-A)") (class "Default")
      (node (ref "LED50") (pin "1") (pinfunction "A_1") (pintype "passive"))
      (node (ref "R50") (pin "1") (pinfunction "1_1") (pintype "passive"))
    )
    (net (code "159") (name "Net-(LED51-A)") (class "Default")
      (node (ref "LED51") (pin "1") (pinfunction "A_1") (pintype "passive"))
      (node (ref "R51") (pin "1") (pinfunction "1_1") (pintype "passive"))
    )
    (net (code "160") (name "Net-(LED52-A)") (class "Default")
      (node (ref "LED52") (pin "1") (pinfunction "A_1") (pintype "passive"))
      (node (ref "R52") (pin "1") (pinfunction "1_1") (pintype "passive"))
    )
    (net (code "161") (name "Net-(LED53-A)") (class "Default")
      (node (ref "LED53") (pin "1") (pinfunction "A_1") (pintype "passive"))
      (node (ref "R53") (pin "1") (pinfunction "1_1") (pintype "passive"))
    )
    (net (code "162") (name "Net-(LED54-A)") (class "Default")
      (node (ref "LED54") (pin "1") (pinfunction "A_1") (pintype "passive"))
      (node (ref "R54") (pin "1") (pinfunction "1_1") (pintype "passive"))
    )
    (net (code "163") (name "Net-(LED55-A)") (class "Default")
      (node (ref "LED55") (pin "1") (pinfunction "A_1") (pintype "passive"))
      (node (ref "R55") (pin "1") (pinfunction "1_1") (pintype "passive"))
    )
    (net (code "164") (name "Net-(LED56-A)") (class "Default")
      (node (ref "LED56") (pin "1") (pinfunction "A_1") (pintype "passive"))
      (node (ref "R56") (pin "1") (pinfunction "1_1") (pintype "passive"))
    )
    (net (code "165") (name "Net-(LED58-A)") (class "Default")
      (node (ref "LED58") (pin "1") (pinfunction "A_1") (pintype "passive"))
      (node (ref "R100") (pin "P$2") (pinfunction "2_P$2") (pintype "passive"))
      (node (ref "U17") (pin "1") (pinfunction "B(2)_1") (pintype "input"))
    )
    (net (code "166") (name "Net-(LED58-C)") (class "Default")
      (node (ref "LED58") (pin "2") (pinfunction "C_2") (pintype "passive"))
      (node (ref "R102") (pin "P$2") (pinfunction "2_P$2") (pintype "passive"))
      (node (ref "SW18") (pin "1") (pinfunction "1_1") (pintype "passive"))
      (node (ref "SW18") (pin "2") (pinfunction "2_2") (pintype "passive"))
    )
    (net (code "167") (name "Net-(LED60-A)") (class "Default")
      (node (ref "LED60") (pin "1") (pinfunction "A_1") (pintype "passive"))
      (node (ref "R106") (pin "P$2") (pinfunction "2_P$2") (pintype "passive"))
      (node (ref "U20") (pin "1") (pinfunction "B(2)_1") (pintype "input"))
    )
    (net (code "168") (name "Net-(LED60-C)") (class "Default")
      (node (ref "LED60") (pin "2") (pinfunction "C_2") (pintype "passive"))
      (node (ref "R108") (pin "P$2") (pinfunction "2_P$2") (pintype "passive"))
      (node (ref "SW20") (pin "1") (pinfunction "1_1") (pintype "passive"))
      (node (ref "SW20") (pin "2") (pinfunction "2_2") (pintype "passive"))
    )
    (net (code "169") (name "Net-(LED65-A)") (class "Default")
      (node (ref "LED65") (pin "1") (pinfunction "A_1") (pintype "passive"))
      (node (ref "R65") (pin "1") (pinfunction "1_1") (pintype "passive"))
    )
    (net (code "170") (name "Net-(LED66-A)") (class "Default")
      (node (ref "LED66") (pin "1") (pinfunction "A_1") (pintype "passive"))
      (node (ref "R66") (pin "1") (pinfunction "1_1") (pintype "passive"))
    )
    (net (code "171") (name "Net-(LED67-A)") (class "Default")
      (node (ref "LED67") (pin "1") (pinfunction "A_1") (pintype "passive"))
      (node (ref "R67") (pin "1") (pinfunction "1_1") (pintype "passive"))
    )
    (net (code "172") (name "Net-(LED68-A)") (class "Default")
      (node (ref "LED68") (pin "1") (pinfunction "A_1") (pintype "passive"))
      (node (ref "R68") (pin "1") (pinfunction "1_1") (pintype "passive"))
    )
    (net (code "173") (name "Net-(LED69-A)") (class "Default")
      (node (ref "LED69") (pin "1") (pinfunction "A_1") (pintype "passive"))
      (node (ref "R69") (pin "1") (pinfunction "1_1") (pintype "passive"))
    )
    (net (code "174") (name "Net-(LED70-A)") (class "Default")
      (node (ref "LED70") (pin "1") (pinfunction "A_1") (pintype "passive"))
      (node (ref "R70") (pin "1") (pinfunction "1_1") (pintype "passive"))
    )
    (net (code "175") (name "Net-(LED71-A)") (class "Default")
      (node (ref "LED71") (pin "1") (pinfunction "A_1") (pintype "passive"))
      (node (ref "R71") (pin "1") (pinfunction "1_1") (pintype "passive"))
    )
    (net (code "176") (name "Net-(LED72-A)") (class "Default")
      (node (ref "LED72") (pin "1") (pinfunction "A_1") (pintype "passive"))
      (node (ref "R72") (pin "1") (pinfunction "1_1") (pintype "passive"))
    )
    (net (code "177") (name "Net-(R28-2)") (class "Default")
      (node (ref "R28") (pin "P$2") (pinfunction "2_P$2") (pintype "passive"))
      (node (ref "U1") (pin "2") (pinfunction "E(1)_2") (pintype "output"))
    )
    (net (code "178") (name "Net-(R42-2)") (class "Default")
      (node (ref "R42") (pin "P$2") (pinfunction "2_P$2") (pintype "passive"))
      (node (ref "U3") (pin "2") (pinfunction "E(1)_2") (pintype "output"))
    )
    (net (code "179") (name "Net-(R48-2)") (class "Default")
      (node (ref "R48") (pin "P$2") (pinfunction "2_P$2") (pintype "passive"))
      (node (ref "U5") (pin "2") (pinfunction "E(1)_2") (pintype "output"))
    )
    (net (code "180") (name "Net-(R63-2)") (class "Default")
      (node (ref "R63") (pin "P$2") (pinfunction "2_P$2") (pintype "passive"))
      (node (ref "U7") (pin "2") (pinfunction "E(1)_2") (pintype "output"))
    )
    (net (code "181") (name "Net-(R77-2)") (class "Default")
      (node (ref "R77") (pin "P$2") (pinfunction "2_P$2") (pintype "passive"))
      (node (ref "U9") (pin "2") (pinfunction "E(1)_2") (pintype "output"))
    )
    (net (code "182") (name "Net-(R83-2)") (class "Default")
      (node (ref "R83") (pin "P$2") (pinfunction "2_P$2") (pintype "passive"))
      (node (ref "U11") (pin "2") (pinfunction "E(1)_2") (pintype "output"))
    )
    (net (code "183") (name "Net-(R89-2)") (class "Default")
      (node (ref "R89") (pin "P$2") (pinfunction "2_P$2") (pintype "passive"))
      (node (ref "U13") (pin "2") (pinfunction "E(1)_2") (pintype "output"))
    )
    (net (code "184") (name "Net-(R95-2)") (class "Default")
      (node (ref "R95") (pin "P$2") (pinfunction "2_P$2") (pintype "passive"))
      (node (ref "U15") (pin "2") (pinfunction "E(1)_2") (pintype "output"))
    )
    (net (code "185") (name "Net-(R101-2)") (class "Default")
      (node (ref "R101") (pin "P$2") (pinfunction "2_P$2") (pintype "passive"))
      (node (ref "U17") (pin "2") (pinfunction "E(1)_2") (pintype "output"))
    )
    (net (code "186") (name "Net-(R107-2)") (class "Default")
      (node (ref "R107") (pin "P$2") (pinfunction "2_P$2") (pintype "passive"))
      (node (ref "U20") (pin "2") (pinfunction "E(1)_2") (pintype "output"))
    )
  )
)
